# V3_B0317.net
KiCad netlist of a schematic drawn in Altium Designer
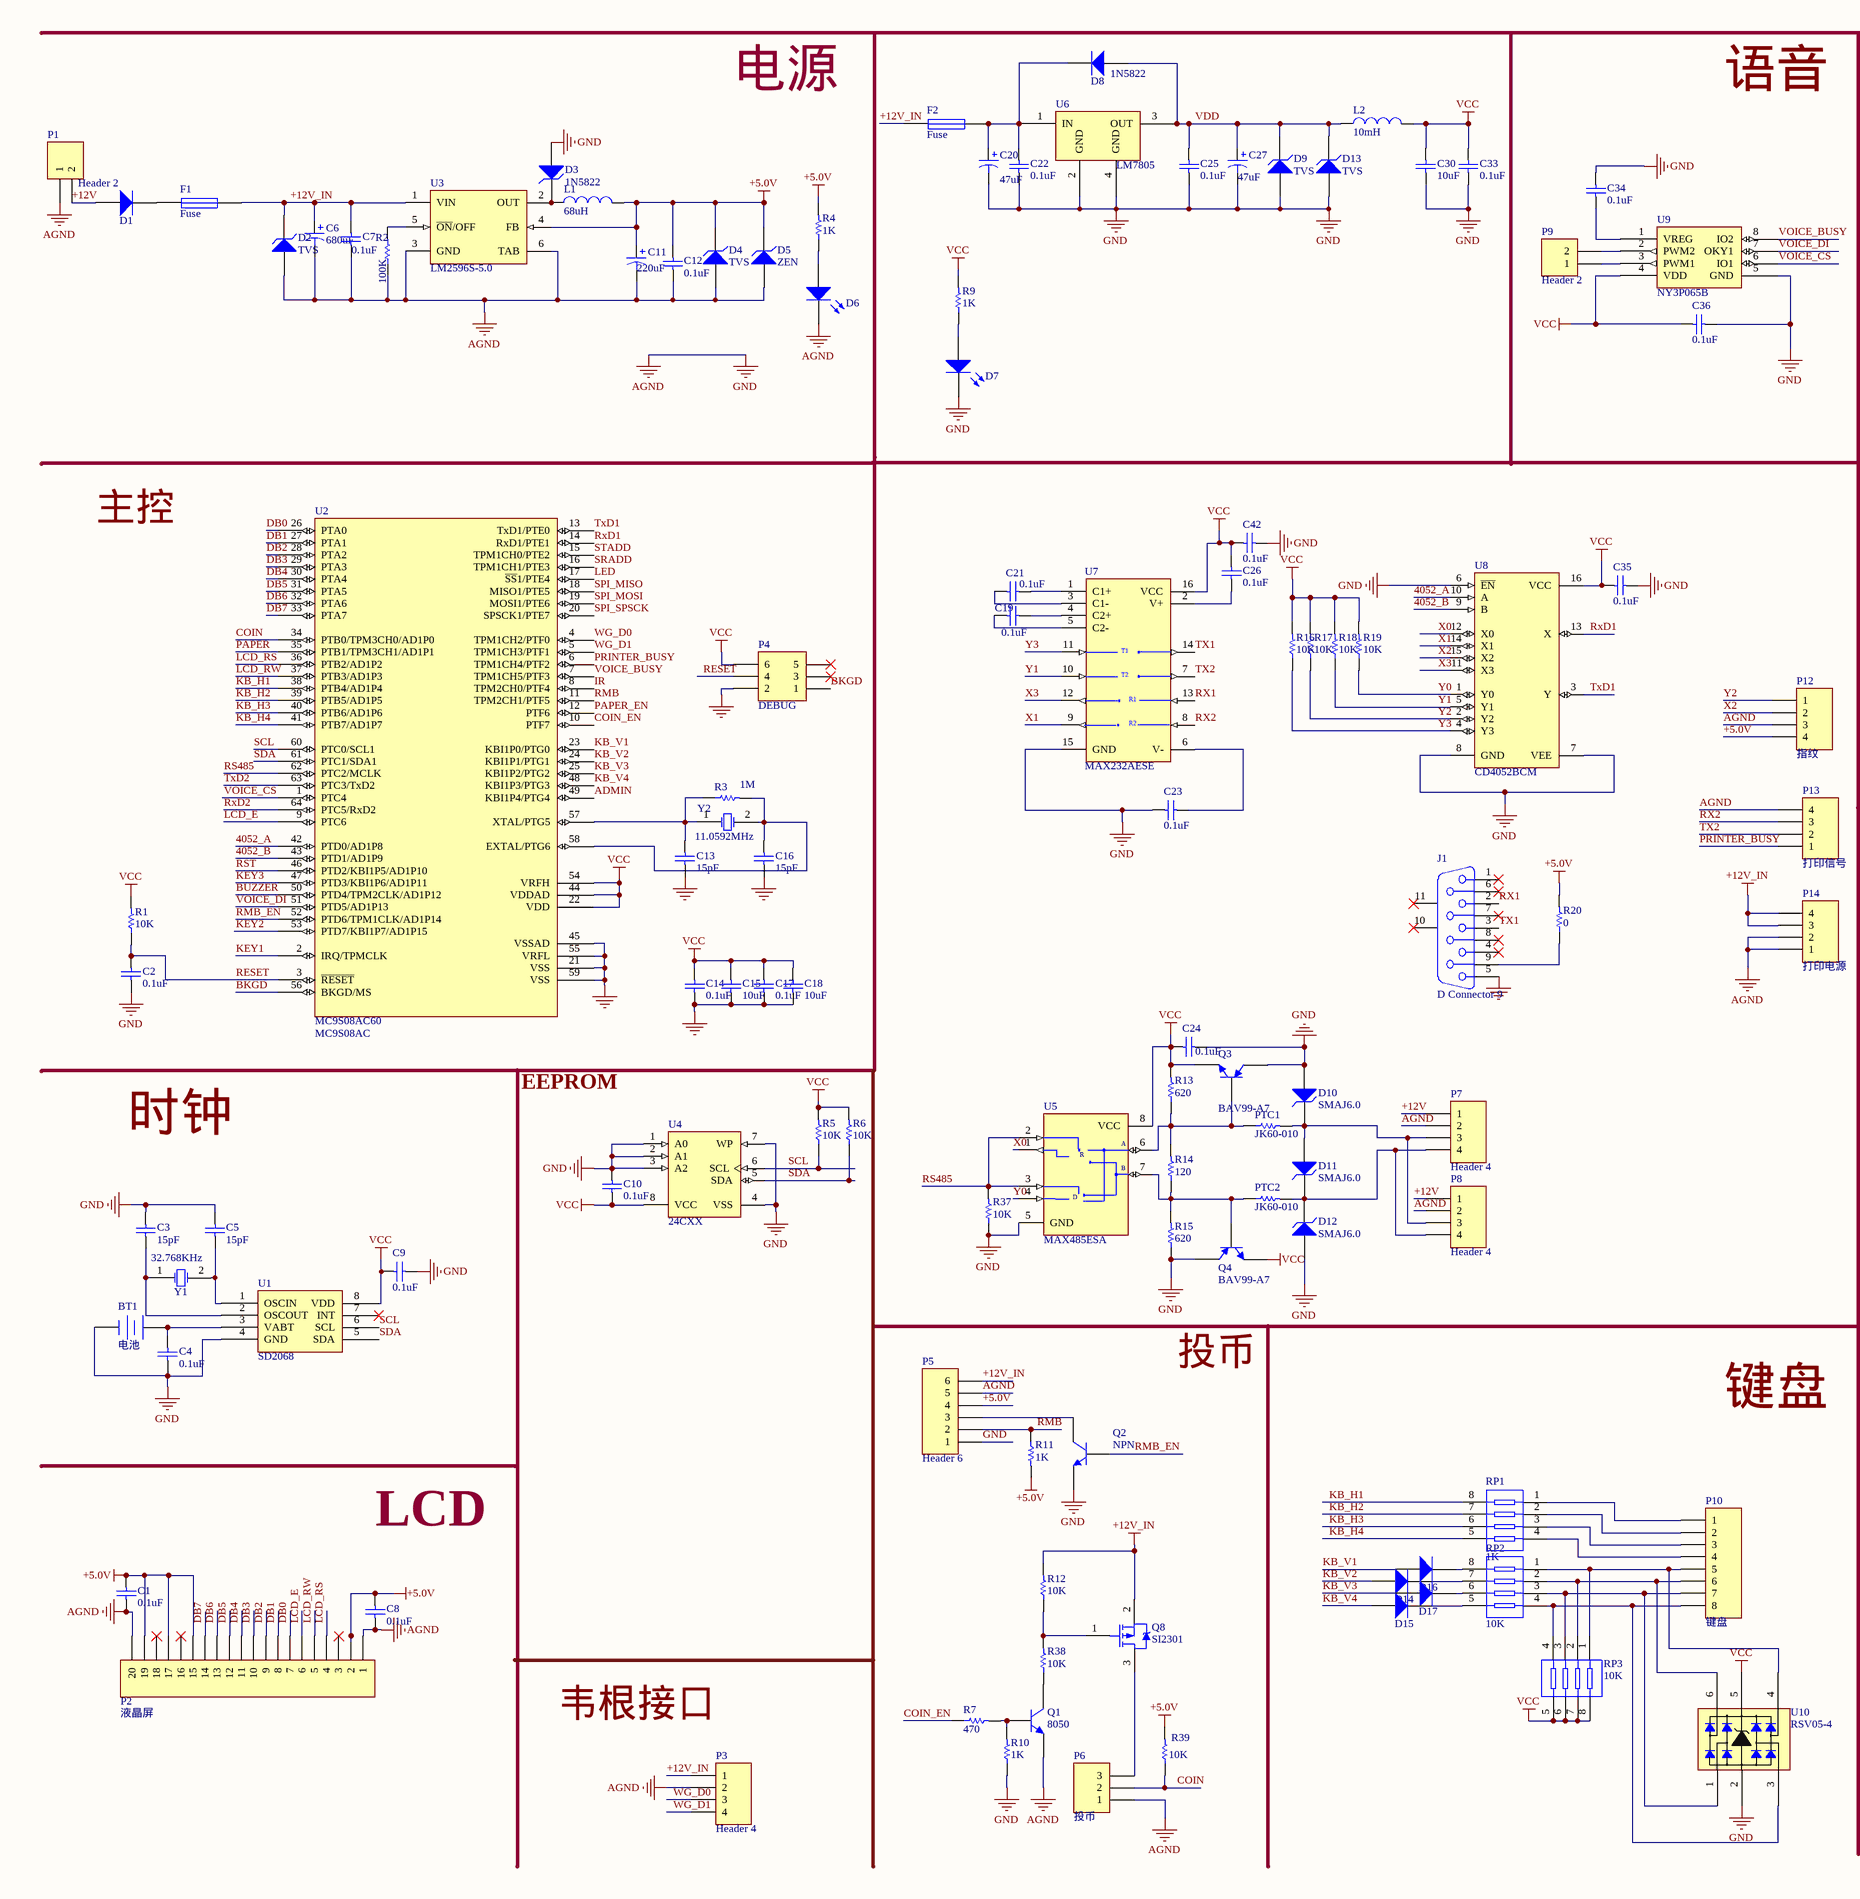
[diagram p0: V3(B0317).SchDoc, left]
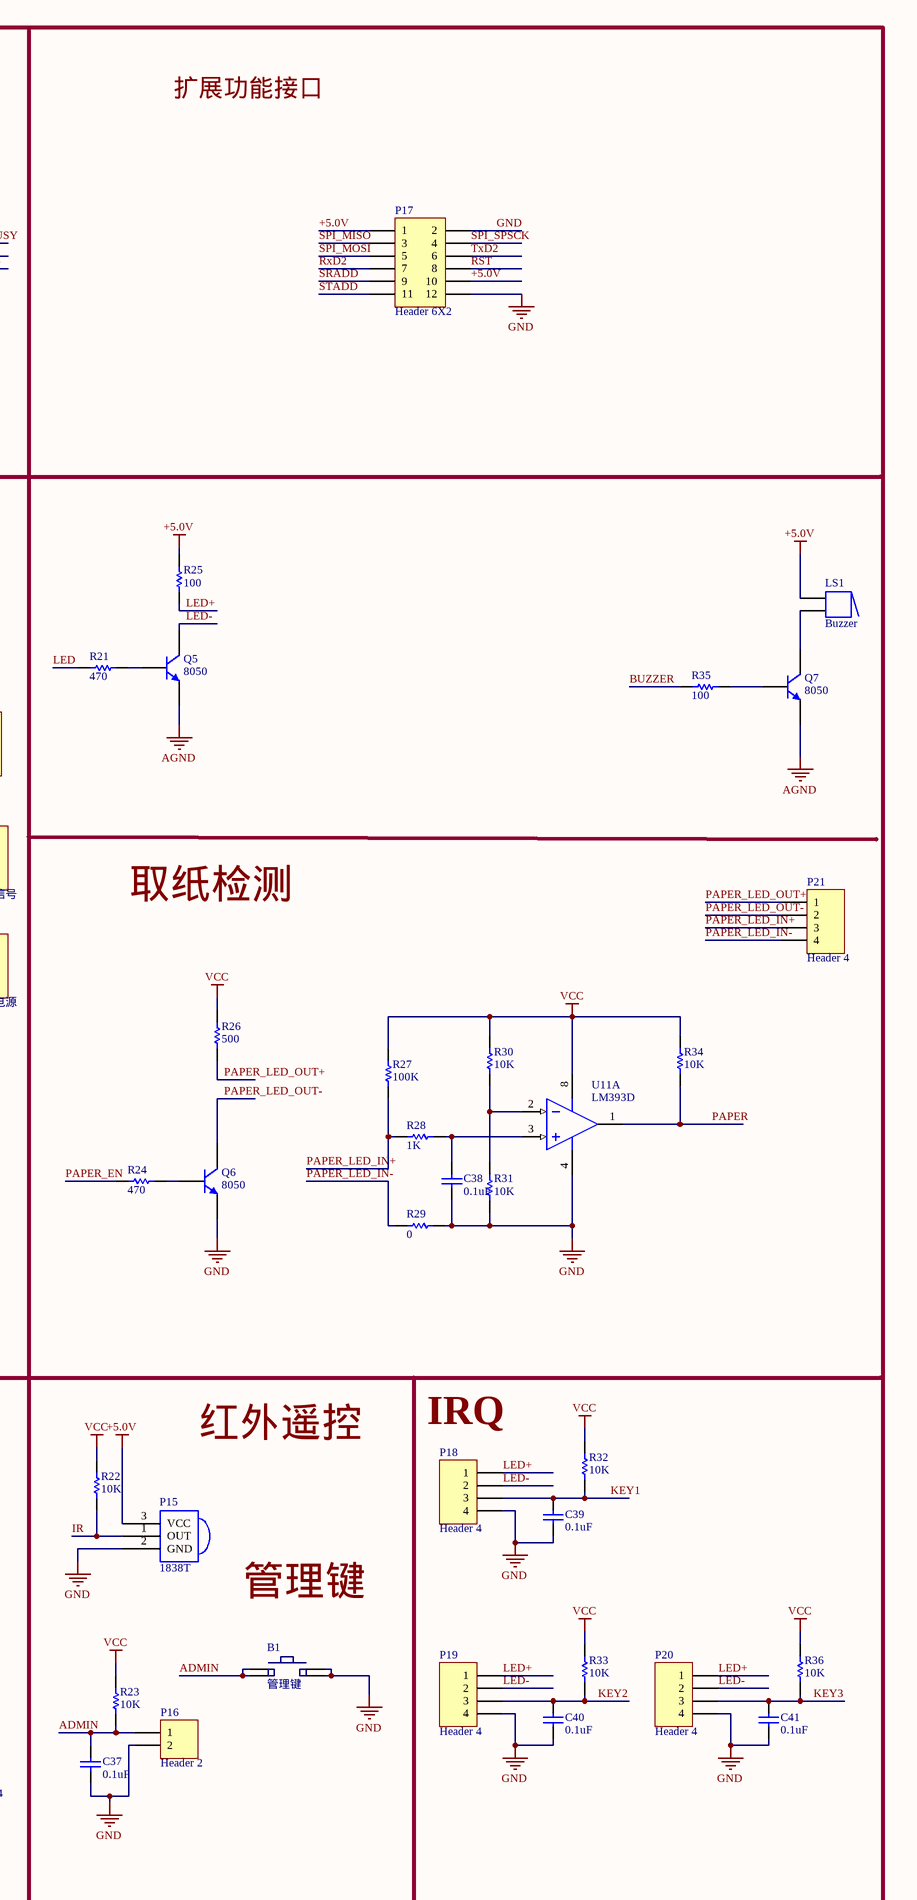
[diagram p1: V3(B0317).SchDoc, right]

(export (version "E")
  (design (tool "Eeschema 10.0.6"))
  (components
    (comp (ref "B1")
      (value "管理键")
      (footprint "AN66")
      (description "Button")
      (libsource (lib "device") (part "Button"))
    )
    (comp (ref "BT1")
      (value "电池")
      (footprint "CR1220")
      (description "Multicell Battery")
      (fields (field (name "PUBLISHER") "Altium Limited"))
      (libsource (lib "device") (part "Battery"))
    )
    (comp (ref "C1")
      (value "0.1uF")
      (footprint "CAPC2012M")
      (description "Capacitor")
      (fields (field (name "PUBLISHER") "Altium Limited"))
      (libsource (lib "device") (part "Cap"))
    )
    (comp (ref "C2")
      (value "0.1uF")
      (footprint "CAPC2012M")
      (description "Capacitor")
      (fields (field (name "PUBLISHER") "Altium Limited"))
      (libsource (lib "device") (part "Cap"))
    )
    (comp (ref "C3")
      (value "15pF")
      (footprint "CAPC2012M")
      (description "Capacitor")
      (fields (field (name "PUBLISHER") "Altium Limited"))
      (libsource (lib "device") (part "Cap"))
    )
    (comp (ref "C4")
      (value "0.1uF")
      (footprint "CAPC2012M")
      (description "Capacitor")
      (fields (field (name "PUBLISHER") "Altium Limited"))
      (libsource (lib "device") (part "Cap"))
    )
    (comp (ref "C5")
      (value "15pF")
      (footprint "CAPC2012M")
      (description "Capacitor")
      (fields (field (name "PUBLISHER") "Altium Limited"))
      (libsource (lib "device") (part "Cap"))
    )
    (comp (ref "C6")
      (value "680uF")
      (footprint "CAPPR2-5x11.5")
      (description "Polarized Capacitor (22uf-47uf)")
      (fields (field (name "Comment") "Cap Pol2") (field (name "PUBLISHER") "Altium Limited"))
      (libsource (lib "device") (part "Cap Pol2"))
    )
    (comp (ref "C7")
      (value "0.1uF")
      (footprint "CAPC2012M")
      (description "Capacitor")
      (fields (field (name "PUBLISHER") "Altium Limited"))
      (libsource (lib "device") (part "Cap"))
    )
    (comp (ref "C8")
      (value "0.1uF")
      (footprint "CAPC2012M")
      (description "Capacitor")
      (fields (field (name "PUBLISHER") "Altium Limited"))
      (libsource (lib "device") (part "Cap"))
    )
    (comp (ref "C9")
      (value "0.1uF")
      (footprint "CAPC2012M")
      (description "Capacitor")
      (fields (field (name "PUBLISHER") "Altium Limited"))
      (libsource (lib "device") (part "Cap"))
    )
    (comp (ref "C10")
      (value "0.1uF")
      (footprint "CAPC2012M")
      (description "Capacitor")
      (fields (field (name "PUBLISHER") "Altium Limited"))
      (libsource (lib "device") (part "Cap"))
    )
    (comp (ref "C11")
      (value "220uF")
      (footprint "CAPPR2-5x11.5")
      (description "Polarized Capacitor (22uf-47uf)")
      (fields (field (name "Comment") "Cap Pol2") (field (name "PUBLISHER") "Altium Limited"))
      (libsource (lib "device") (part "Cap Pol2"))
    )
    (comp (ref "C12")
      (value "0.1uF")
      (footprint "CAPC2012M")
      (description "Capacitor")
      (fields (field (name "PUBLISHER") "Altium Limited"))
      (libsource (lib "device") (part "Cap"))
    )
    (comp (ref "C13")
      (value "15pF")
      (footprint "CAPC2012M")
      (description "Capacitor")
      (fields (field (name "PUBLISHER") "Altium Limited"))
      (libsource (lib "device") (part "Cap"))
    )
    (comp (ref "C14")
      (value "0.1uF")
      (footprint "CAPC2012M")
      (description "Capacitor")
      (fields (field (name "PUBLISHER") "Altium Limited"))
      (libsource (lib "device") (part "Cap"))
    )
    (comp (ref "C15")
      (value "10uF")
      (footprint "CAPC2012M")
      (description "Capacitor")
      (fields (field (name "PUBLISHER") "Altium Limited"))
      (libsource (lib "device") (part "Cap"))
    )
    (comp (ref "C16")
      (value "15pF")
      (footprint "CAPC2012M")
      (description "Capacitor")
      (fields (field (name "PUBLISHER") "Altium Limited"))
      (libsource (lib "device") (part "Cap"))
    )
    (comp (ref "C17")
      (value "0.1uF")
      (footprint "CAPC2012M")
      (description "Capacitor")
      (fields (field (name "PUBLISHER") "Altium Limited"))
      (libsource (lib "device") (part "Cap"))
    )
    (comp (ref "C18")
      (value "10uF")
      (footprint "CAPC2012M")
      (description "Capacitor")
      (fields (field (name "PUBLISHER") "Altium Limited"))
      (libsource (lib "device") (part "Cap"))
    )
    (comp (ref "C19")
      (value "0.1uF")
      (footprint "CAPC2012M")
      (description "Capacitor")
      (fields (field (name "PUBLISHER") "Altium Limited"))
      (libsource (lib "device") (part "Cap"))
    )
    (comp (ref "C20")
      (value "47uF")
      (footprint "CAPPR2-5x11.5")
      (description "Polarized Capacitor (22uf-47uf)")
      (fields (field (name "Comment") "Cap Pol2") (field (name "PUBLISHER") "Altium Limited"))
      (libsource (lib "device") (part "Cap Pol2"))
    )
    (comp (ref "C21")
      (value "0.1uF")
      (footprint "CAPC2012M")
      (description "Capacitor")
      (fields (field (name "PUBLISHER") "Altium Limited"))
      (libsource (lib "device") (part "Cap"))
    )
    (comp (ref "C22")
      (value "0.1uF")
      (footprint "CAPC2012M")
      (description "Capacitor")
      (fields (field (name "PUBLISHER") "Altium Limited"))
      (libsource (lib "device") (part "Cap"))
    )
    (comp (ref "C23")
      (value "0.1uF")
      (footprint "CAPC2012M")
      (description "Capacitor")
      (fields (field (name "PUBLISHER") "Altium Limited"))
      (libsource (lib "device") (part "Cap"))
    )
    (comp (ref "C24")
      (value "0.1uF")
      (footprint "CAPC2012M")
      (description "Capacitor")
      (fields (field (name "PUBLISHER") "Altium Limited"))
      (libsource (lib "device") (part "Cap"))
    )
    (comp (ref "C25")
      (value "0.1uF")
      (footprint "CAPC2012M")
      (description "Capacitor")
      (fields (field (name "PUBLISHER") "Altium Limited"))
      (libsource (lib "device") (part "Cap"))
    )
    (comp (ref "C26")
      (value "0.1uF")
      (footprint "CAPC2012M")
      (description "Capacitor")
      (fields (field (name "PUBLISHER") "Altium Limited"))
      (libsource (lib "device") (part "Cap"))
    )
    (comp (ref "C27")
      (value "47uF")
      (footprint "CAPPR2-5x11.5")
      (description "Polarized Capacitor (22uf-47uf)")
      (fields (field (name "Comment") "Cap Pol2") (field (name "PUBLISHER") "Altium Limited"))
      (libsource (lib "device") (part "Cap Pol2"))
    )
    (comp (ref "C30")
      (value "10uF")
      (footprint "CAPC2012M")
      (description "Capacitor")
      (fields (field (name "PUBLISHER") "Altium Limited"))
      (libsource (lib "device") (part "Cap"))
    )
    (comp (ref "C33")
      (value "0.1uF")
      (footprint "CAPC2012M")
      (description "Capacitor")
      (fields (field (name "PUBLISHER") "Altium Limited"))
      (libsource (lib "device") (part "Cap"))
    )
    (comp (ref "C34")
      (value "0.1uF")
      (footprint "CAPC2012M")
      (description "Capacitor")
      (fields (field (name "PUBLISHER") "Altium Limited"))
      (libsource (lib "device") (part "Cap"))
    )
    (comp (ref "C35")
      (value "0.1uF")
      (footprint "CAPC2012M")
      (description "Capacitor")
      (fields (field (name "PUBLISHER") "Altium Limited"))
      (libsource (lib "device") (part "Cap"))
    )
    (comp (ref "C36")
      (value "0.1uF")
      (footprint "CAPC2012M")
      (description "Capacitor")
      (fields (field (name "PUBLISHER") "Altium Limited"))
      (libsource (lib "device") (part "Cap"))
    )
    (comp (ref "C37")
      (value "0.1uF")
      (footprint "CAPC2012M")
      (description "Capacitor")
      (fields (field (name "PUBLISHER") "Altium Limited"))
      (libsource (lib "device") (part "Cap"))
    )
    (comp (ref "C38")
      (value "0.1uF")
      (footprint "CAPC2012M")
      (description "Capacitor")
      (fields (field (name "PUBLISHER") "Altium Limited"))
      (libsource (lib "device") (part "Cap"))
    )
    (comp (ref "C39")
      (value "0.1uF")
      (footprint "CAPC2012M")
      (description "Capacitor")
      (fields (field (name "PUBLISHER") "Altium Limited"))
      (libsource (lib "device") (part "Cap"))
    )
    (comp (ref "C40")
      (value "0.1uF")
      (footprint "CAPC2012M")
      (description "Capacitor")
      (fields (field (name "PUBLISHER") "Altium Limited"))
      (libsource (lib "device") (part "Cap"))
    )
    (comp (ref "C41")
      (value "0.1uF")
      (footprint "CAPC2012M")
      (description "Capacitor")
      (fields (field (name "PUBLISHER") "Altium Limited"))
      (libsource (lib "device") (part "Cap"))
    )
    (comp (ref "C42")
      (value "0.1uF")
      (footprint "CAPC2012M")
      (description "Capacitor")
      (fields (field (name "PUBLISHER") "Altium Limited"))
      (libsource (lib "device") (part "Cap"))
    )
    (comp (ref "D1")
      (value "Diode")
      (footprint "DSO-C2/X1.8")
      (description "Default Diode")
      (fields (field (name "PUBLISHER") "Altium Limited"))
      (libsource (lib "device") (part "Diode"))
    )
    (comp (ref "D2")
      (value "TVS")
      (footprint "DSO-C2/X1.8")
      (description "TVS瞬态抑制二极管")
      (fields (field (name "PUBLISHER") "Altium Limited"))
      (libsource (lib "device") (part "TVS"))
    )
    (comp (ref "D3")
      (value "1N5822")
      (footprint "DSO-C2/X1.8")
      (description "TVS瞬态抑制二极管")
      (fields (field (name "PUBLISHER") "Altium Limited"))
      (libsource (lib "device") (part "TVS"))
    )
    (comp (ref "D4")
      (value "TVS")
      (footprint "DSO-C2/X1.8")
      (description "TVS瞬态抑制二极管")
      (fields (field (name "PUBLISHER") "Altium Limited"))
      (libsource (lib "device") (part "TVS"))
    )
    (comp (ref "D5")
      (value "ZEN")
      (footprint "DIO1206")
      (description "TVS瞬态抑制二极管")
      (fields (field (name "PUBLISHER") "Altium Limited"))
      (libsource (lib "device") (part "TVS"))
    )
    (comp (ref "D6")
      (value "LED")
      (footprint "LED2012M")
      (description "Typical INFRARED GaAs LED")
      (fields (field (name "PUBLISHER") "Altium Limited"))
      (libsource (lib "device") (part "LED"))
    )
    (comp (ref "D7")
      (value "LED")
      (footprint "LED2012M")
      (description "Typical INFRARED GaAs LED")
      (fields (field (name "PUBLISHER") "Altium Limited"))
      (libsource (lib "device") (part "LED"))
    )
    (comp (ref "D8")
      (value "1N5822")
      (footprint "DSO-C2/X1.8")
      (description "Default Diode")
      (fields (field (name "PUBLISHER") "Altium Limited"))
      (libsource (lib "device") (part "Diode"))
    )
    (comp (ref "D9")
      (value "TVS")
      (footprint "DSO-C2/X1.8")
      (description "TVS瞬态抑制二极管")
      (fields (field (name "PUBLISHER") "Altium Limited"))
      (libsource (lib "device") (part "TVS"))
    )
    (comp (ref "D10")
      (value "SMAJ6.0")
      (footprint "DSO-C2/X1.8")
      (description "TVS瞬态抑制二极管")
      (fields (field (name "PUBLISHER") "Altium Limited"))
      (libsource (lib "device") (part "TVS"))
    )
    (comp (ref "D11")
      (value "SMAJ6.0")
      (footprint "DSO-C2/X1.8")
      (description "TVS瞬态抑制二极管")
      (fields (field (name "PUBLISHER") "Altium Limited"))
      (libsource (lib "device") (part "TVS"))
    )
    (comp (ref "D12")
      (value "SMAJ6.0")
      (footprint "DSO-C2/X1.8")
      (description "TVS瞬态抑制二极管")
      (fields (field (name "PUBLISHER") "Altium Limited"))
      (libsource (lib "device") (part "TVS"))
    )
    (comp (ref "D13")
      (value "TVS")
      (footprint "DIO1206")
      (description "TVS瞬态抑制二极管")
      (fields (field (name "PUBLISHER") "Altium Limited"))
      (libsource (lib "device") (part "TVS"))
    )
    (comp (ref "D14")
      (value "1N4007")
      (footprint "SOD123")
      (description "Default Diode")
      (fields (field (name "PUBLISHER") "Altium Limited"))
      (libsource (lib "device") (part "Diode"))
    )
    (comp (ref "D15")
      (value "1N4007")
      (footprint "SOD123")
      (description "Default Diode")
      (fields (field (name "PUBLISHER") "Altium Limited"))
      (libsource (lib "device") (part "Diode"))
    )
    (comp (ref "D16")
      (value "1N4007")
      (footprint "SOD123")
      (description "Default Diode")
      (fields (field (name "PUBLISHER") "Altium Limited"))
      (libsource (lib "device") (part "Diode"))
    )
    (comp (ref "D17")
      (value "1N4007")
      (footprint "SOD123")
      (description "Default Diode")
      (fields (field (name "PUBLISHER") "Altium Limited"))
      (libsource (lib "device") (part "Diode"))
    )
    (comp (ref "F1")
      (value "Fuse")
      (footprint "SR075")
      (fields (field (name "PUBLISHER") "Altium Limited"))
      (libsource (lib "device") (part "Fuse"))
    )
    (comp (ref "F2")
      (value "Fuse")
      (footprint "FUSE1206N")
      (fields (field (name "PUBLISHER") "Altium Limited"))
      (libsource (lib "device") (part "Fuse"))
    )
    (comp (ref "J1")
      (value "D Connector 9")
      (footprint "DSUB1.385-2H9")
      (description "Receptacle Assembly, 9 Position, Right Angle")
      (fields (field (name "PUBLISHER") "Altium Limited"))
      (libsource (lib "connector") (part "D Connector 9"))
    )
    (comp (ref "L1")
      (value "68uH")
      (footprint "INDUCTOR-9*12")
      (description "Inductor")
      (fields (field (name "PUBLISHER") "Altium Limited"))
      (libsource (lib "device") (part "Inductor"))
    )
    (comp (ref "L2")
      (value "10mH")
      (footprint "INDC2012M")
      (description "Inductor")
      (fields (field (name "PUBLISHER") "Altium Limited"))
      (libsource (lib "device") (part "Inductor"))
    )
    (comp (ref "LS1")
      (value "Buzzer")
      (footprint "BELL")
      (description "Magnetic Transducer Buzzer")
      (fields (field (name "PUBLISHER") "Altium Limited"))
      (libsource (lib "device") (part "Buzzer"))
    )
    (comp (ref "P1")
      (value "Header 2")
      (footprint "VH396-2")
      (description "Header, 2-Pin")
      (fields (field (name "PUBLISHER") "Altium Limited"))
      (libsource (lib "") (part "Header 2_1"))
    )
    (comp (ref "P2")
      (value "液晶屏")
      (footprint "LCD12864")
      (description "Header, 20-Pin")
      (fields (field (name "PUBLISHER") "Altium Limited"))
      (libsource (lib "connector") (part "Header 20"))
    )
    (comp (ref "P3")
      (value "Header 4")
      (footprint "XH254-4")
      (description "Header, 4-Pin")
      (fields (field (name "PUBLISHER") "Altium Limited"))
      (libsource (lib "connector") (part "Header 4"))
    )
    (comp (ref "P4")
      (value "DEBUG")
      (footprint "HDR2X3")
      (description "Header, 3-Pin, Dual row")
      (fields (field (name "PUBLISHER") "Altium Limited"))
      (libsource (lib "connector") (part "Header 3X2"))
    )
    (comp (ref "P5")
      (value "Header 6")
      (footprint "XH254-6")
      (description "Header, 6-Pin")
      (fields (field (name "PUBLISHER") "Altium Limited"))
      (libsource (lib "connector") (part "Header 6"))
    )
    (comp (ref "P6")
      (value "投币")
      (footprint "XH254-3")
      (description "Header, 3-Pin")
      (fields (field (name "PUBLISHER") "Altium Limited"))
      (libsource (lib "connector") (part "Header 3"))
    )
    (comp (ref "P7")
      (value "Header 4")
      (footprint "VH396-4")
      (description "Header, 4-Pin")
      (fields (field (name "PUBLISHER") "Altium Limited"))
      (libsource (lib "connector") (part "Header 4"))
    )
    (comp (ref "P8")
      (value "Header 4")
      (footprint "VH396-4")
      (description "Header, 4-Pin")
      (fields (field (name "PUBLISHER") "Altium Limited"))
      (libsource (lib "connector") (part "Header 4"))
    )
    (comp (ref "P9")
      (value "Header 2")
      (footprint "XH254-2")
      (description "Header, 2-Pin")
      (fields (field (name "PUBLISHER") "Altium Limited"))
      (libsource (lib "connector") (part "Header 2"))
    )
    (comp (ref "P10")
      (value "键盘")
      (footprint "XH254-8")
      (description "Header, 8-Pin")
      (fields (field (name "PUBLISHER") "Altium Limited"))
      (libsource (lib "connector") (part "Header 8"))
    )
    (comp (ref "P12")
      (value "指纹")
      (footprint "XH254-4")
      (description "Header, 4-Pin")
      (fields (field (name "PUBLISHER") "Altium Limited"))
      (libsource (lib "connector") (part "Header 4"))
    )
    (comp (ref "P13")
      (value "打印信号")
      (footprint "XH254-4")
      (description "Header, 4-Pin")
      (fields (field (name "PUBLISHER") "Altium Limited"))
      (libsource (lib "") (part "Header 4_2"))
    )
    (comp (ref "P14")
      (value "打印电源")
      (footprint "XH254-4")
      (description "Header, 4-Pin")
      (fields (field (name "PUBLISHER") "Altium Limited"))
      (libsource (lib "") (part "Header 4_2"))
    )
    (comp (ref "P15") (value "1838T") (footprint "XH254-3") (libsource (lib "device") (part "1838T")))
    (comp (ref "P16")
      (value "Header 2")
      (footprint "XH254-2")
      (description "Header, 2-Pin")
      (fields (field (name "PUBLISHER") "Altium Limited"))
      (libsource (lib "") (part "Header 2_2"))
    )
    (comp (ref "P17")
      (value "Header 6X2")
      (footprint "HDR2X6")
      (description "Header, 6-Pin, Dual row")
      (fields (field (name "PUBLISHER") "Altium Limited"))
      (libsource (lib "Miscellaneous Connectors") (part "Header 6X2"))
    )
    (comp (ref "P18")
      (value "Header 4")
      (footprint "XH254-4")
      (description "Header, 4-Pin")
      (fields (field (name "PUBLISHER") "Altium Limited"))
      (libsource (lib "") (part "Header 4_1"))
    )
    (comp (ref "P19")
      (value "Header 4")
      (footprint "XH254-4")
      (description "Header, 4-Pin")
      (fields (field (name "PUBLISHER") "Altium Limited"))
      (libsource (lib "") (part "Header 4_1"))
    )
    (comp (ref "P20")
      (value "Header 4")
      (footprint "XH254-4")
      (description "Header, 4-Pin")
      (fields (field (name "PUBLISHER") "Altium Limited"))
      (libsource (lib "") (part "Header 4_1"))
    )
    (comp (ref "P21")
      (value "Header 4")
      (footprint "XH254-4")
      (description "Header, 4-Pin")
      (fields (field (name "PUBLISHER") "Altium Limited"))
      (libsource (lib "connector") (part "Header 4"))
    )
    (comp (ref "PTC1")
      (value "JK60-010")
      (footprint "RESC2012M")
      (description "Resistor")
      (fields (field (name "PUBLISHER") "Altium Limited"))
      (libsource (lib "device") (part "Res"))
    )
    (comp (ref "PTC2")
      (value "JK60-010")
      (footprint "RESC2012M")
      (description "Resistor")
      (fields (field (name "PUBLISHER") "Altium Limited"))
      (libsource (lib "device") (part "Res"))
    )
    (comp (ref "Q1")
      (value "8050")
      (footprint "SOT23-3M")
      (description "NPN Bipolar Transistor")
      (fields (field (name "PUBLISHER") "Altium Limited"))
      (libsource (lib "device") (part "NPN"))
    )
    (comp (ref "Q2")
      (value "NPN")
      (footprint "SOT23-3M")
      (description "NPN Bipolar Transistor")
      (fields (field (name "PUBLISHER") "Altium Limited"))
      (libsource (lib "device") (part "NPN"))
    )
    (comp (ref "Q3") (value "BAV99-A7") (footprint "SOT23-3M") (libsource (lib "device") (part "BAV99-A7")))
    (comp (ref "Q4") (value "BAV99-A7") (footprint "SOT23-3M") (libsource (lib "device") (part "BAV99-A7")))
    (comp (ref "Q5")
      (value "8050")
      (footprint "SOT23-3M")
      (description "NPN Bipolar Transistor")
      (fields (field (name "PUBLISHER") "Altium Limited"))
      (libsource (lib "device") (part "NPN"))
    )
    (comp (ref "Q6")
      (value "8050")
      (footprint "SOT23-3M")
      (description "NPN Bipolar Transistor")
      (fields (field (name "PUBLISHER") "Altium Limited"))
      (libsource (lib "device") (part "NPN"))
    )
    (comp (ref "Q7")
      (value "8050")
      (footprint "SOT23-3M")
      (description "NPN Bipolar Transistor")
      (fields (field (name "PUBLISHER") "Altium Limited"))
      (libsource (lib "device") (part "NPN"))
    )
    (comp (ref "Q8") (value "SI2301") (footprint "SOT23-3M") (libsource (lib "device") (part "SI2301")))
    (comp (ref "R1")
      (value "10K")
      (footprint "RESC2012M")
      (description "Resistor")
      (fields (field (name "PUBLISHER") "Altium Limited"))
      (libsource (lib "device") (part "Res"))
    )
    (comp (ref "R2")
      (value "100K")
      (footprint "RESC2012M")
      (description "Resistor")
      (fields (field (name "PUBLISHER") "Altium Limited"))
      (libsource (lib "device") (part "Res"))
    )
    (comp (ref "R3")
      (value "1M")
      (footprint "RESC2012M")
      (description "Resistor")
      (fields (field (name "PUBLISHER") "Altium Limited"))
      (libsource (lib "device") (part "Res"))
    )
    (comp (ref "R4")
      (value "1K")
      (footprint "RESC2012M")
      (description "Resistor")
      (fields (field (name "PUBLISHER") "Altium Limited"))
      (libsource (lib "device") (part "Res"))
    )
    (comp (ref "R5")
      (value "10K")
      (footprint "RESC2012M")
      (description "Resistor")
      (fields (field (name "PUBLISHER") "Altium Limited"))
      (libsource (lib "device") (part "Res"))
    )
    (comp (ref "R6")
      (value "10K")
      (footprint "RESC2012M")
      (description "Resistor")
      (fields (field (name "PUBLISHER") "Altium Limited"))
      (libsource (lib "device") (part "Res"))
    )
    (comp (ref "R7")
      (value "470")
      (footprint "RESC2012M")
      (description "Resistor")
      (fields (field (name "PUBLISHER") "Altium Limited"))
      (libsource (lib "device") (part "Res"))
    )
    (comp (ref "R9")
      (value "1K")
      (footprint "RESC2012M")
      (description "Resistor")
      (fields (field (name "PUBLISHER") "Altium Limited"))
      (libsource (lib "device") (part "Res"))
    )
    (comp (ref "R10")
      (value "1K")
      (footprint "RESC2012M")
      (description "Resistor")
      (fields (field (name "PUBLISHER") "Altium Limited"))
      (libsource (lib "device") (part "Res"))
    )
    (comp (ref "R11")
      (value "1K")
      (footprint "RESC2012M")
      (description "Resistor")
      (fields (field (name "PUBLISHER") "Altium Limited"))
      (libsource (lib "device") (part "Res"))
    )
    (comp (ref "R12")
      (value "10K")
      (footprint "RESC2012M")
      (description "Resistor")
      (fields (field (name "PUBLISHER") "Altium Limited"))
      (libsource (lib "device") (part "Res"))
    )
    (comp (ref "R13")
      (value "620")
      (footprint "RESC2012M")
      (description "Resistor")
      (fields (field (name "PUBLISHER") "Altium Limited"))
      (libsource (lib "device") (part "Res"))
    )
    (comp (ref "R14")
      (value "120")
      (footprint "RESC2012M")
      (description "Resistor")
      (fields (field (name "PUBLISHER") "Altium Limited"))
      (libsource (lib "device") (part "Res"))
    )
    (comp (ref "R15")
      (value "620")
      (footprint "RESC2012M")
      (description "Resistor")
      (fields (field (name "PUBLISHER") "Altium Limited"))
      (libsource (lib "device") (part "Res"))
    )
    (comp (ref "R16")
      (value "10K")
      (footprint "RESC2012M")
      (description "Resistor")
      (fields (field (name "PUBLISHER") "Altium Limited"))
      (libsource (lib "device") (part "Res"))
    )
    (comp (ref "R17")
      (value "10K")
      (footprint "RESC2012M")
      (description "Resistor")
      (fields (field (name "PUBLISHER") "Altium Limited"))
      (libsource (lib "device") (part "Res"))
    )
    (comp (ref "R18")
      (value "10K")
      (footprint "RESC2012M")
      (description "Resistor")
      (fields (field (name "PUBLISHER") "Altium Limited"))
      (libsource (lib "device") (part "Res"))
    )
    (comp (ref "R19")
      (value "10K")
      (footprint "RESC2012M")
      (description "Resistor")
      (fields (field (name "PUBLISHER") "Altium Limited"))
      (libsource (lib "device") (part "Res"))
    )
    (comp (ref "R20")
      (value "0")
      (footprint "RESC2012M")
      (description "Resistor")
      (fields (field (name "PUBLISHER") "Altium Limited"))
      (libsource (lib "device") (part "Res"))
    )
    (comp (ref "R21")
      (value "470")
      (footprint "RESC2012M")
      (description "Resistor")
      (fields (field (name "PUBLISHER") "Altium Limited"))
      (libsource (lib "device") (part "Res"))
    )
    (comp (ref "R22")
      (value "10K")
      (footprint "RESC2012M")
      (description "Resistor")
      (fields (field (name "PUBLISHER") "Altium Limited"))
      (libsource (lib "device") (part "Res"))
    )
    (comp (ref "R23")
      (value "10K")
      (footprint "RESC2012M")
      (description "Resistor")
      (fields (field (name "PUBLISHER") "Altium Limited"))
      (libsource (lib "device") (part "Res"))
    )
    (comp (ref "R24")
      (value "470")
      (footprint "RESC2012M")
      (description "Resistor")
      (fields (field (name "PUBLISHER") "Altium Limited"))
      (libsource (lib "device") (part "Res"))
    )
    (comp (ref "R25")
      (value "100")
      (footprint "RESC2012M")
      (description "Resistor")
      (fields (field (name "PUBLISHER") "Altium Limited"))
      (libsource (lib "device") (part "Res"))
    )
    (comp (ref "R26")
      (value "500")
      (footprint "RESC2012M")
      (description "Resistor")
      (fields (field (name "PUBLISHER") "Altium Limited"))
      (libsource (lib "device") (part "Res"))
    )
    (comp (ref "R27")
      (value "100K")
      (footprint "RESC2012M")
      (description "Resistor")
      (fields (field (name "PUBLISHER") "Altium Limited"))
      (libsource (lib "device") (part "Res"))
    )
    (comp (ref "R28")
      (value "1K")
      (footprint "RESC2012M")
      (description "Resistor")
      (fields (field (name "PUBLISHER") "Altium Limited"))
      (libsource (lib "device") (part "Res"))
    )
    (comp (ref "R29")
      (value "0")
      (footprint "RESC2012M")
      (description "Resistor")
      (fields (field (name "PUBLISHER") "Altium Limited"))
      (libsource (lib "device") (part "Res"))
    )
    (comp (ref "R30")
      (value "10K")
      (footprint "RESC2012M")
      (description "Resistor")
      (fields (field (name "PUBLISHER") "Altium Limited"))
      (libsource (lib "device") (part "Res"))
    )
    (comp (ref "R31")
      (value "10K")
      (footprint "RESC2012M")
      (description "Resistor")
      (fields (field (name "PUBLISHER") "Altium Limited"))
      (libsource (lib "device") (part "Res"))
    )
    (comp (ref "R32")
      (value "10K")
      (footprint "RESC2012M")
      (description "Resistor")
      (fields (field (name "PUBLISHER") "Altium Limited"))
      (libsource (lib "device") (part "Res"))
    )
    (comp (ref "R33")
      (value "10K")
      (footprint "RESC2012M")
      (description "Resistor")
      (fields (field (name "PUBLISHER") "Altium Limited"))
      (libsource (lib "device") (part "Res"))
    )
    (comp (ref "R34")
      (value "10K")
      (footprint "RESC2012M")
      (description "Resistor")
      (fields (field (name "PUBLISHER") "Altium Limited"))
      (libsource (lib "device") (part "Res"))
    )
    (comp (ref "R35")
      (value "100")
      (footprint "RESC2012M")
      (description "Resistor")
      (fields (field (name "PUBLISHER") "Altium Limited"))
      (libsource (lib "device") (part "Res"))
    )
    (comp (ref "R36")
      (value "10K")
      (footprint "RESC2012M")
      (description "Resistor")
      (fields (field (name "PUBLISHER") "Altium Limited"))
      (libsource (lib "device") (part "Res"))
    )
    (comp (ref "R37")
      (value "10K")
      (footprint "RESC2012M")
      (description "Resistor")
      (fields (field (name "PUBLISHER") "Altium Limited"))
      (libsource (lib "device") (part "Res"))
    )
    (comp (ref "R38")
      (value "10K")
      (footprint "RESC2012M")
      (description "Resistor")
      (fields (field (name "PUBLISHER") "Altium Limited"))
      (libsource (lib "device") (part "Res"))
    )
    (comp (ref "R39")
      (value "10K")
      (footprint "RESC2012M")
      (description "Resistor")
      (fields (field (name "PUBLISHER") "Altium Limited"))
      (libsource (lib "device") (part "Res"))
    )
    (comp (ref "RP1") (value "1K") (footprint "EXB38V") (libsource (lib "device") (part "Res Pack")))
    (comp (ref "RP2") (value "10K") (footprint "EXB38V") (libsource (lib "device") (part "Res Pack")))
    (comp (ref "RP3") (value "10K") (footprint "EXB38V") (libsource (lib "device") (part "Res Pack")))
    (comp (ref "U1")
      (value "SD2068")
      (footprint "SO8_M")
      (description "实时时钟")
      (libsource (lib "ic") (part "SD2068"))
    )
    (comp (ref "U2")
      (value "MC9S08AC60")
      (footprint "QFP80P1720X1720-64N")
      (description "HCS08 MC9S08AC60")
      (fields (field (name "ALTIUM_VALUE") "MC9S08AC"))
      (libsource (lib "ic") (part "MC9S08AC60"))
    )
    (comp (ref "U3")
      (value "LM2596S-5.0")
      (footprint "TS5B_N")
      (description "SIMPLE SWITCHER?Power Converter 150 KHz 3A Step-Down Voltage Regulator, 5-pin TO-263")
      (fields
        (field (name "MANUFACTURER") "National Semiconductor")
        (field (name "PUBLISHER") "Altium Limited")
      )
      (libsource (lib "ic") (part "LM2596S-5.0"))
    )
    (comp (ref "U4")
      (value "24CXX")
      (footprint "SO8_M")
      (description "5V, I2C Serial EEPROM")
      (fields (field (name "PUBLISHER") "Altium Limited"))
      (libsource (lib "ic") (part "24CXX"))
    )
    (comp (ref "U5")
      (value "MAX485ESA")
      (footprint "SO8_M")
      (description "Low-Power, Slew-Rate-Limited RS-485/RS-422 Transceiver")
      (fields (field (name "PUBLISHER") "Altium Limited"))
      (libsource (lib "ic") (part "MAX485ESA"))
    )
    (comp (ref "U6") (value "LM7805") (footprint "SOT223-4M") (libsource (lib "ic") (part "LM7805")))
    (comp (ref "U7")
      (value "MAX232AESE")
      (footprint "SO16_M")
      (description "+5V-Powered, Multichannel RS-232 Driver/Receiver")
      (fields (field (name "PUBLISHER") "Altium Limited"))
      (libsource (lib "ic") (part "MAX232AESE"))
    )
    (comp (ref "U8")
      (value "CD4052BCM")
      (footprint "SO16_M")
      (description "Dual 4-Channel Analog Multiplexer/Demultiplexer")
      (fields (field (name "PUBLISHER") "Altium Limited"))
      (libsource (lib "ic") (part "CD4052BCM"))
    )
    (comp (ref "U9") (value "NY3P065B") (footprint "DIP-8") (libsource (lib "ic") (part "NY3P065B")))
    (comp (ref "U10")
      (value "RSV05-4")
      (footprint "SOT26A-6M")
      (description "USB OR  Ethernet ESD")
      (libsource (lib "device") (part "RSV05-4"))
    )
    (comp (ref "U11")
      (value "LM393D")
      (footprint "SO8_M")
      (description "Low-Power Dual Voltage Comparator")
      (fields (field (name "PUBLISHER") "Altium Limited"))
      (libsource (lib "ic") (part "LM393D"))
    )
    (comp (ref "Y1")
      (value "32.768KHz")
      (footprint "XTAL-W2/D2.1")
      (description "Crystal Oscillator")
      (fields (field (name "Comment") "XTAL") (field (name "PUBLISHER") "Altium Limited"))
      (libsource (lib "device") (part "XTAL"))
    )
    (comp (ref "Y2")
      (value "11.0592MHz")
      (footprint "HC49_TH")
      (description "Crystal Oscillator")
      (fields (field (name "Comment") "XTAL") (field (name "PUBLISHER") "Altium Limited"))
      (libsource (lib "device") (part "XTAL"))
    )
  )
  (nets
    (net (code "1") (name "+5.0V") (class "Default")
      (node (ref "C1") (pin "2") (pinfunction "2_2") (pintype "passive"))
      (node (ref "C11") (pin "1") (pinfunction "1_1") (pintype "passive"))
      (node (ref "C12") (pin "2") (pinfunction "2_2") (pintype "passive"))
      (node (ref "C8") (pin "2") (pinfunction "2_2") (pintype "passive"))
      (node (ref "D4") (pin "2") (pinfunction "K_2") (pintype "passive"))
      (node (ref "D5") (pin "2") (pinfunction "K_2") (pintype "passive"))
      (node (ref "L1") (pin "2") (pinfunction "2_2") (pintype "passive"))
      (node (ref "LS1") (pin "1") (pinfunction "1_1") (pintype "passive"))
      (node (ref "P12") (pin "4") (pinfunction "4_4") (pintype "passive"))
      (node (ref "P15") (pin "3") (pinfunction "VCC_3") (pintype "passive"))
      (node (ref "P17") (pin "1") (pinfunction "1_1") (pintype "passive"))
      (node (ref "P17") (pin "10") (pinfunction "10_10") (pintype "passive"))
      (node (ref "P2") (pin "15") (pinfunction "15_15") (pintype "passive"))
      (node (ref "P2") (pin "17") (pinfunction "17_17") (pintype "passive"))
      (node (ref "P2") (pin "19") (pinfunction "19_19") (pintype "passive"))
      (node (ref "P2") (pin "2") (pinfunction "2_2") (pintype "passive"))
      (node (ref "P5") (pin "4") (pinfunction "4_4") (pintype "passive"))
      (node (ref "R11") (pin "2") (pinfunction "2_2") (pintype "passive"))
      (node (ref "R20") (pin "2") (pinfunction "2_2") (pintype "passive"))
      (node (ref "R25") (pin "2") (pinfunction "2_2") (pintype "passive"))
      (node (ref "R39") (pin "2") (pinfunction "2_2") (pintype "passive"))
      (node (ref "R4") (pin "2") (pinfunction "2_2") (pintype "passive"))
      (node (ref "U3") (pin "4") (pinfunction "FB_4") (pintype "input"))
    )
    (net (code "2") (name "+12V_IN") (class "Default")
      (node (ref "C6") (pin "1") (pinfunction "1_1") (pintype "passive"))
      (node (ref "C7") (pin "2") (pinfunction "2_2") (pintype "passive"))
      (node (ref "D2") (pin "2") (pinfunction "K_2") (pintype "passive"))
      (node (ref "F1") (pin "2") (pinfunction "2_2") (pintype "passive"))
      (node (ref "F2") (pin "1") (pinfunction "1_1") (pintype "passive"))
      (node (ref "P14") (pin "3") (pinfunction "3_3") (pintype "passive"))
      (node (ref "P14") (pin "4") (pinfunction "4_4") (pintype "passive"))
      (node (ref "P3") (pin "1") (pinfunction "1_1") (pintype "passive"))
      (node (ref "P5") (pin "6") (pinfunction "6_6") (pintype "passive"))
      (node (ref "Q8") (pin "2") (pinfunction "S_2") (pintype "passive"))
      (node (ref "R12") (pin "2") (pinfunction "2_2") (pintype "passive"))
      (node (ref "U3") (pin "1") (pinfunction "VIN_1") (pintype "power_in"))
    )
    (net (code "3") (name "/+12V") (class "Default")
      (node (ref "D1") (pin "1") (pinfunction "A_1") (pintype "passive"))
      (node (ref "P1") (pin "2") (pinfunction "2_2") (pintype "passive"))
      (node (ref "P7") (pin "1") (pinfunction "1_1") (pintype "passive"))
      (node (ref "P8") (pin "1") (pinfunction "1_1") (pintype "passive"))
    )
    (net (code "4") (name "/4052_A") (class "Default")
      (node (ref "U2") (pin "42") (pinfunction "PTD0/AD1P8_42") (pintype "bidirectional"))
      (node (ref "U8") (pin "10") (pinfunction "A_10") (pintype "input"))
    )
    (net (code "5") (name "/4052_B") (class "Default")
      (node (ref "U2") (pin "43") (pinfunction "PTD1/AD1P9_43") (pintype "bidirectional"))
      (node (ref "U8") (pin "9") (pinfunction "B_9") (pintype "input"))
    )
    (net (code "6") (name "/ADMIN") (class "Default")
      (node (ref "B1") (pin "1") (pintype "passive"))
      (node (ref "B1") (pin "3") (pintype "passive"))
      (node (ref "C37") (pin "2") (pinfunction "2_2") (pintype "passive"))
      (node (ref "P16") (pin "1") (pinfunction "1_1") (pintype "passive"))
      (node (ref "R23") (pin "1") (pinfunction "1_1") (pintype "passive"))
      (node (ref "U2") (pin "49") (pinfunction "KBI1P4/PTG4_49") (pintype "bidirectional"))
    )
    (net (code "7") (name "/BKGD") (class "Default")
      (node (ref "P4") (pin "1") (pinfunction "1_1") (pintype "passive"))
      (node (ref "U2") (pin "56") (pinfunction "BKGD/MS_56") (pintype "bidirectional"))
    )
    (net (code "8") (name "/BUZZER") (class "Default")
      (node (ref "R35") (pin "1") (pinfunction "1_1") (pintype "passive"))
      (node (ref "U2") (pin "50") (pinfunction "PTD4/TPM2CLK/AD1P12_50") (pintype "bidirectional"))
    )
    (net (code "9") (name "/COIN") (class "Default")
      (node (ref "P6") (pin "2") (pinfunction "2_2") (pintype "passive"))
      (node (ref "R39") (pin "1") (pinfunction "1_1") (pintype "passive"))
      (node (ref "U2") (pin "34") (pinfunction "PTB0/TPM3CH0/AD1P0_34") (pintype "bidirectional"))
    )
    (net (code "10") (name "/COIN_EN") (class "Default")
      (node (ref "R7") (pin "1") (pinfunction "1_1") (pintype "passive"))
      (node (ref "U2") (pin "10") (pinfunction "PTF7_10") (pintype "bidirectional"))
    )
    (net (code "11") (name "/DB0") (class "Default")
      (node (ref "P2") (pin "7") (pinfunction "7_7") (pintype "passive"))
      (node (ref "U2") (pin "26") (pinfunction "PTA0_26") (pintype "bidirectional"))
    )
    (net (code "12") (name "/DB1") (class "Default")
      (node (ref "P2") (pin "8") (pinfunction "8_8") (pintype "passive"))
      (node (ref "U2") (pin "27") (pinfunction "PTA1_27") (pintype "bidirectional"))
    )
    (net (code "13") (name "/DB2") (class "Default")
      (node (ref "P2") (pin "9") (pinfunction "9_9") (pintype "passive"))
      (node (ref "U2") (pin "28") (pinfunction "PTA2_28") (pintype "bidirectional"))
    )
    (net (code "14") (name "/DB3") (class "Default")
      (node (ref "P2") (pin "10") (pinfunction "10_10") (pintype "passive"))
      (node (ref "U2") (pin "29") (pinfunction "PTA3_29") (pintype "bidirectional"))
    )
    (net (code "15") (name "/DB4") (class "Default")
      (node (ref "P2") (pin "11") (pinfunction "11_11") (pintype "passive"))
      (node (ref "U2") (pin "30") (pinfunction "PTA4_30") (pintype "bidirectional"))
    )
    (net (code "16") (name "/DB5") (class "Default")
      (node (ref "P2") (pin "12") (pinfunction "12_12") (pintype "passive"))
      (node (ref "U2") (pin "31") (pinfunction "PTA5_31") (pintype "bidirectional"))
    )
    (net (code "17") (name "/DB6") (class "Default")
      (node (ref "P2") (pin "13") (pinfunction "13_13") (pintype "passive"))
      (node (ref "U2") (pin "32") (pinfunction "PTA6_32") (pintype "bidirectional"))
    )
    (net (code "18") (name "/DB7") (class "Default")
      (node (ref "P2") (pin "14") (pinfunction "14_14") (pintype "passive"))
      (node (ref "U2") (pin "33") (pinfunction "PTA7_33") (pintype "bidirectional"))
    )
    (net (code "19") (name "/IR") (class "Default")
      (node (ref "P15") (pin "1") (pinfunction "OUT_1") (pintype "passive"))
      (node (ref "R22") (pin "1") (pinfunction "1_1") (pintype "passive"))
      (node (ref "U2") (pin "8") (pinfunction "TPM2CH0/PTF4_8") (pintype "bidirectional"))
    )
    (net (code "20") (name "/KB_H1") (class "Default")
      (node (ref "RP1") (pin "8") (pinfunction "8_8") (pintype "passive"))
      (node (ref "U2") (pin "38") (pinfunction "PTB4/AD1P4_38") (pintype "bidirectional"))
    )
    (net (code "21") (name "/KB_H2") (class "Default")
      (node (ref "RP1") (pin "7") (pinfunction "7_7") (pintype "passive"))
      (node (ref "U2") (pin "39") (pinfunction "PTB5/AD1P5_39") (pintype "bidirectional"))
    )
    (net (code "22") (name "/KB_H3") (class "Default")
      (node (ref "RP1") (pin "6") (pinfunction "6_6") (pintype "passive"))
      (node (ref "U2") (pin "40") (pinfunction "PTB6/AD1P6_40") (pintype "bidirectional"))
    )
    (net (code "23") (name "/KB_H4") (class "Default")
      (node (ref "RP1") (pin "5") (pinfunction "5_5") (pintype "passive"))
      (node (ref "U2") (pin "41") (pinfunction "PTB7/AD1P7_41") (pintype "bidirectional"))
    )
    (net (code "24") (name "/KB_V1") (class "Default")
      (node (ref "D16") (pin "1") (pinfunction "A_1") (pintype "passive"))
      (node (ref "U2") (pin "23") (pinfunction "KBI1P0/PTG0_23") (pintype "bidirectional"))
    )
    (net (code "25") (name "/KB_V2") (class "Default")
      (node (ref "D14") (pin "1") (pinfunction "A_1") (pintype "passive"))
      (node (ref "U2") (pin "24") (pinfunction "KBI1P1/PTG1_24") (pintype "bidirectional"))
    )
    (net (code "26") (name "/KB_V3") (class "Default")
      (node (ref "D17") (pin "1") (pinfunction "A_1") (pintype "passive"))
      (node (ref "U2") (pin "25") (pinfunction "KBI1P2/PTG2_25") (pintype "bidirectional"))
    )
    (net (code "27") (name "/KB_V4") (class "Default")
      (node (ref "D15") (pin "1") (pinfunction "A_1") (pintype "passive"))
      (node (ref "U2") (pin "48") (pinfunction "KBI1P3/PTG3_48") (pintype "bidirectional"))
    )
    (net (code "28") (name "/KEY1") (class "Default")
      (node (ref "C39") (pin "2") (pinfunction "2_2") (pintype "passive"))
      (node (ref "P18") (pin "3") (pinfunction "3_3") (pintype "passive"))
      (node (ref "R32") (pin "1") (pinfunction "1_1") (pintype "passive"))
      (node (ref "U2") (pin "2") (pinfunction "IRQ/TPMCLK_2") (pintype "bidirectional"))
    )
    (net (code "29") (name "/KEY2") (class "Default")
      (node (ref "C40") (pin "2") (pinfunction "2_2") (pintype "passive"))
      (node (ref "P19") (pin "3") (pinfunction "3_3") (pintype "passive"))
      (node (ref "R33") (pin "1") (pinfunction "1_1") (pintype "passive"))
      (node (ref "U2") (pin "53") (pinfunction "PTD7/KBI1P7/AD1P15_53") (pintype "bidirectional"))
    )
    (net (code "30") (name "/KEY3") (class "Default")
      (node (ref "C41") (pin "2") (pinfunction "2_2") (pintype "passive"))
      (node (ref "P20") (pin "3") (pinfunction "3_3") (pintype "passive"))
      (node (ref "R36") (pin "1") (pinfunction "1_1") (pintype "passive"))
      (node (ref "U2") (pin "47") (pinfunction "PTD3/KBI1P6/AD1P11_47") (pintype "bidirectional"))
    )
    (net (code "31") (name "/LCD_E") (class "Default")
      (node (ref "P2") (pin "6") (pinfunction "6_6") (pintype "passive"))
      (node (ref "U2") (pin "9") (pinfunction "PTC6_9") (pintype "bidirectional"))
    )
    (net (code "32") (name "/LCD_RS") (class "Default")
      (node (ref "P2") (pin "4") (pinfunction "4_4") (pintype "passive"))
      (node (ref "U2") (pin "36") (pinfunction "PTB2/AD1P2_36") (pintype "bidirectional"))
    )
    (net (code "33") (name "/LCD_RW") (class "Default")
      (node (ref "P2") (pin "5") (pinfunction "5_5") (pintype "passive"))
      (node (ref "U2") (pin "37") (pinfunction "PTB3/AD1P3_37") (pintype "bidirectional"))
    )
    (net (code "34") (name "/LED") (class "Default")
      (node (ref "R21") (pin "1") (pinfunction "1_1") (pintype "passive"))
      (node (ref "U2") (pin "17") (pinfunction "~{SS}1/PTE4_17") (pintype "bidirectional"))
    )
    (net (code "35") (name "/LED+") (class "Default")
      (node (ref "P18") (pin "1") (pinfunction "1_1") (pintype "passive"))
      (node (ref "P19") (pin "1") (pinfunction "1_1") (pintype "passive"))
      (node (ref "P20") (pin "1") (pinfunction "1_1") (pintype "passive"))
      (node (ref "R25") (pin "1") (pinfunction "1_1") (pintype "passive"))
    )
    (net (code "36") (name "/LED-") (class "Default")
      (node (ref "P18") (pin "2") (pinfunction "2_2") (pintype "passive"))
      (node (ref "P19") (pin "2") (pinfunction "2_2") (pintype "passive"))
      (node (ref "P20") (pin "2") (pinfunction "2_2") (pintype "passive"))
      (node (ref "Q5") (pin "3") (pinfunction "C_3") (pintype "passive"))
    )
    (net (code "37") (name "/PAPER") (class "Default")
      (node (ref "R34") (pin "1") (pinfunction "1_1") (pintype "passive"))
      (node (ref "U11") (pin "1") (pinfunction "OUT_1") (pintype "open_collector"))
      (node (ref "U2") (pin "35") (pinfunction "PTB1/TPM3CH1/AD1P1_35") (pintype "bidirectional"))
    )
    (net (code "38") (name "/PAPER_EN") (class "Default")
      (node (ref "R24") (pin "1") (pinfunction "1_1") (pintype "passive"))
      (node (ref "U2") (pin "12") (pinfunction "PTF6_12") (pintype "bidirectional"))
    )
    (net (code "39") (name "/PAPER_LED_IN+") (class "Default")
      (node (ref "P21") (pin "3") (pinfunction "3_3") (pintype "passive"))
      (node (ref "R27") (pin "1") (pinfunction "1_1") (pintype "passive"))
      (node (ref "R28") (pin "1") (pinfunction "1_1") (pintype "passive"))
    )
    (net (code "40") (name "/PAPER_LED_IN-") (class "Default")
      (node (ref "P21") (pin "4") (pinfunction "4_4") (pintype "passive"))
      (node (ref "R29") (pin "1") (pinfunction "1_1") (pintype "passive"))
    )
    (net (code "41") (name "/PAPER_LED_OUT+") (class "Default")
      (node (ref "P21") (pin "1") (pinfunction "1_1") (pintype "passive"))
      (node (ref "R26") (pin "1") (pinfunction "1_1") (pintype "passive"))
    )
    (net (code "42") (name "/PAPER_LED_OUT-") (class "Default")
      (node (ref "P21") (pin "2") (pinfunction "2_2") (pintype "passive"))
      (node (ref "Q6") (pin "3") (pinfunction "C_3") (pintype "passive"))
    )
    (net (code "43") (name "/PRINTER_BUSY") (class "Default")
      (node (ref "P13") (pin "1") (pinfunction "1_1") (pintype "passive"))
      (node (ref "U2") (pin "6") (pinfunction "TPM1CH4/PTF2_6") (pintype "bidirectional"))
    )
    (net (code "44") (name "/RESET") (class "Default")
      (node (ref "C2") (pin "2") (pinfunction "2_2") (pintype "passive"))
      (node (ref "P4") (pin "4") (pinfunction "4_4") (pintype "passive"))
      (node (ref "R1") (pin "1") (pinfunction "1_1") (pintype "passive"))
      (node (ref "U2") (pin "3") (pinfunction "~{RESET}_3") (pintype "bidirectional"))
    )
    (net (code "45") (name "/RMB") (class "Default")
      (node (ref "P5") (pin "2") (pinfunction "2_2") (pintype "passive"))
      (node (ref "R11") (pin "1") (pinfunction "1_1") (pintype "passive"))
      (node (ref "U2") (pin "11") (pinfunction "TPM2CH1/PTF5_11") (pintype "bidirectional"))
    )
    (net (code "46") (name "/RMB_EN") (class "Default")
      (node (ref "Q2") (pin "1") (pinfunction "B_1") (pintype "passive"))
      (node (ref "U2") (pin "52") (pinfunction "PTD6/TPM1CLK/AD1P14_52") (pintype "bidirectional"))
    )
    (net (code "47") (name "/RS485") (class "Default")
      (node (ref "R37") (pin "2") (pinfunction "2_2") (pintype "passive"))
      (node (ref "U2") (pin "62") (pinfunction "PTC2/MCLK_62") (pintype "bidirectional"))
      (node (ref "U5") (pin "2") (pinfunction "~{RE}_2") (pintype "input"))
      (node (ref "U5") (pin "3") (pinfunction "DE_3") (pintype "input"))
    )
    (net (code "48") (name "/RST") (class "Default")
      (node (ref "P17") (pin "8") (pinfunction "8_8") (pintype "passive"))
      (node (ref "U2") (pin "46") (pinfunction "PTD2/KBI1P5/AD1P10_46") (pintype "bidirectional"))
    )
    (net (code "49") (name "/RX1") (class "Default")
      (node (ref "J1") (pin "2") (pinfunction "2_2") (pintype "passive"))
      (node (ref "U7") (pin "13") (pinfunction "R1IN_13") (pintype "input"))
    )
    (net (code "50") (name "/RX2") (class "Default")
      (node (ref "P13") (pin "3") (pinfunction "3_3") (pintype "passive"))
      (node (ref "U7") (pin "8") (pinfunction "R2IN_8") (pintype "input"))
    )
    (net (code "51") (name "/RxD1") (class "Default")
      (node (ref "U2") (pin "14") (pinfunction "RxD1/PTE1_14") (pintype "bidirectional"))
      (node (ref "U8") (pin "13") (pinfunction "X_13") (pintype "bidirectional"))
    )
    (net (code "52") (name "/RxD2") (class "Default")
      (node (ref "P17") (pin "7") (pinfunction "7_7") (pintype "passive"))
      (node (ref "U2") (pin "64") (pinfunction "PTC5/RxD2_64") (pintype "bidirectional"))
    )
    (net (code "53") (name "/SCL") (class "Default")
      (node (ref "R5") (pin "1") (pinfunction "1_1") (pintype "passive"))
      (node (ref "U1") (pin "6") (pinfunction "SCL_6") (pintype "passive"))
      (node (ref "U2") (pin "60") (pinfunction "PTC0/SCL1_60") (pintype "bidirectional"))
      (node (ref "U4") (pin "6") (pinfunction "SCL_6") (pintype "input"))
    )
    (net (code "54") (name "/SDA") (class "Default")
      (node (ref "R6") (pin "1") (pinfunction "1_1") (pintype "passive"))
      (node (ref "U1") (pin "5") (pinfunction "SDA_5") (pintype "passive"))
      (node (ref "U2") (pin "61") (pinfunction "PTC1/SDA1_61") (pintype "bidirectional"))
      (node (ref "U4") (pin "5") (pinfunction "SDA_5") (pintype "bidirectional"))
    )
    (net (code "55") (name "/SPI_MISO") (class "Default")
      (node (ref "P17") (pin "3") (pinfunction "3_3") (pintype "passive"))
      (node (ref "U2") (pin "18") (pinfunction "MISO1/PTE5_18") (pintype "bidirectional"))
    )
    (net (code "56") (name "/SPI_MOSI") (class "Default")
      (node (ref "P17") (pin "5") (pinfunction "5_5") (pintype "passive"))
      (node (ref "U2") (pin "19") (pinfunction "MOSI1/PTE6_19") (pintype "bidirectional"))
    )
    (net (code "57") (name "/SPI_SPSCK") (class "Default")
      (node (ref "P17") (pin "4") (pinfunction "4_4") (pintype "passive"))
      (node (ref "U2") (pin "20") (pinfunction "SPSCK1/PTE7_20") (pintype "bidirectional"))
    )
    (net (code "58") (name "/SRADD") (class "Default")
      (node (ref "P17") (pin "9") (pinfunction "9_9") (pintype "passive"))
      (node (ref "U2") (pin "16") (pinfunction "TPM1CH1/PTE3_16") (pintype "bidirectional"))
    )
    (net (code "59") (name "/STADD") (class "Default")
      (node (ref "P17") (pin "11") (pinfunction "11_11") (pintype "passive"))
      (node (ref "U2") (pin "15") (pinfunction "TPM1CH0/PTE2_15") (pintype "bidirectional"))
    )
    (net (code "60") (name "/TX1") (class "Default")
      (node (ref "J1") (pin "3") (pinfunction "3_3") (pintype "passive"))
      (node (ref "U7") (pin "14") (pinfunction "T1OUT_14") (pintype "output"))
    )
    (net (code "61") (name "/TX2") (class "Default")
      (node (ref "P13") (pin "2") (pinfunction "2_2") (pintype "passive"))
      (node (ref "U7") (pin "7") (pinfunction "T2OUT_7") (pintype "output"))
    )
    (net (code "62") (name "/TxD1") (class "Default")
      (node (ref "U2") (pin "13") (pinfunction "TxD1/PTE0_13") (pintype "bidirectional"))
      (node (ref "U8") (pin "3") (pinfunction "Y_3") (pintype "bidirectional"))
    )
    (net (code "63") (name "/TxD2") (class "Default")
      (node (ref "P17") (pin "6") (pinfunction "6_6") (pintype "passive"))
      (node (ref "U2") (pin "63") (pinfunction "PTC3/TxD2_63") (pintype "bidirectional"))
    )
    (net (code "64") (name "/VDD") (class "Default")
      (node (ref "C25") (pin "1") (pinfunction "1_1") (pintype "passive"))
      (node (ref "C27") (pin "1") (pinfunction "1_1") (pintype "passive"))
      (node (ref "D13") (pin "2") (pinfunction "K_2") (pintype "passive"))
      (node (ref "D8") (pin "1") (pinfunction "A_1") (pintype "passive"))
      (node (ref "D9") (pin "2") (pinfunction "K_2") (pintype "passive"))
      (node (ref "L2") (pin "1") (pinfunction "1_1") (pintype "passive"))
      (node (ref "U6") (pin "3") (pinfunction "OUT_3") (pintype "passive"))
    )
    (net (code "65") (name "/VOICE_BUSY") (class "Default")
      (node (ref "U2") (pin "7") (pinfunction "TPM1CH5/PTF3_7") (pintype "bidirectional"))
      (node (ref "U9") (pin "8") (pinfunction "IO2_8") (pintype "bidirectional"))
    )
    (net (code "66") (name "/VOICE_CS") (class "Default")
      (node (ref "U2") (pin "1") (pinfunction "PTC4_1") (pintype "bidirectional"))
      (node (ref "U9") (pin "6") (pinfunction "IO1_6") (pintype "bidirectional"))
    )
    (net (code "67") (name "/VOICE_DI") (class "Default")
      (node (ref "U2") (pin "51") (pinfunction "PTD5/AD1P13_51") (pintype "bidirectional"))
      (node (ref "U9") (pin "7") (pinfunction "OKY1_7") (pintype "bidirectional"))
    )
    (net (code "68") (name "/WG_D0") (class "Default")
      (node (ref "P3") (pin "3") (pinfunction "3_3") (pintype "passive"))
      (node (ref "U2") (pin "4") (pinfunction "TPM1CH2/PTF0_4") (pintype "bidirectional"))
    )
    (net (code "69") (name "/WG_D1") (class "Default")
      (node (ref "P3") (pin "4") (pinfunction "4_4") (pintype "passive"))
      (node (ref "U2") (pin "5") (pinfunction "TPM1CH3/PTF1_5") (pintype "bidirectional"))
    )
    (net (code "70") (name "/X0") (class "Default")
      (node (ref "U5") (pin "1") (pinfunction "RO_1") (pintype "output"))
      (node (ref "U8") (pin "12") (pinfunction "X0_12") (pintype "bidirectional"))
    )
    (net (code "71") (name "/X1") (class "Default")
      (node (ref "U7") (pin "9") (pinfunction "R2OUT_9") (pintype "output"))
      (node (ref "U8") (pin "14") (pinfunction "X1_14") (pintype "bidirectional"))
    )
    (net (code "72") (name "/X2") (class "Default")
      (node (ref "P12") (pin "2") (pinfunction "2_2") (pintype "passive"))
      (node (ref "U8") (pin "15") (pinfunction "X2_15") (pintype "bidirectional"))
    )
    (net (code "73") (name "/X3") (class "Default")
      (node (ref "U7") (pin "12") (pinfunction "R1OUT_12") (pintype "output"))
      (node (ref "U8") (pin "11") (pinfunction "X3_11") (pintype "bidirectional"))
    )
    (net (code "74") (name "/Y0") (class "Default")
      (node (ref "R19") (pin "1") (pinfunction "1_1") (pintype "passive"))
      (node (ref "U5") (pin "4") (pinfunction "DI_4") (pintype "input"))
      (node (ref "U8") (pin "1") (pinfunction "Y0_1") (pintype "bidirectional"))
    )
    (net (code "75") (name "/Y1") (class "Default")
      (node (ref "R18") (pin "1") (pinfunction "1_1") (pintype "passive"))
      (node (ref "U7") (pin "10") (pinfunction "T2IN_10") (pintype "input"))
      (node (ref "U8") (pin "5") (pinfunction "Y1_5") (pintype "bidirectional"))
    )
    (net (code "76") (name "/Y2") (class "Default")
      (node (ref "P12") (pin "1") (pinfunction "1_1") (pintype "passive"))
      (node (ref "R17") (pin "1") (pinfunction "1_1") (pintype "passive"))
      (node (ref "U8") (pin "2") (pinfunction "Y2_2") (pintype "bidirectional"))
    )
    (net (code "77") (name "/Y3") (class "Default")
      (node (ref "R16") (pin "1") (pinfunction "1_1") (pintype "passive"))
      (node (ref "U7") (pin "11") (pinfunction "T1IN_11") (pintype "input"))
      (node (ref "U8") (pin "4") (pinfunction "Y3_4") (pintype "bidirectional"))
    )
    (net (code "78") (name "AGND") (class "Default")
      (node (ref "B1") (pin "2") (pintype "passive"))
      (node (ref "B1") (pin "4") (pintype "passive"))
      (node (ref "BT1") (pin "2") (pinfunction "-_2") (pintype "passive"))
      (node (ref "C1") (pin "1") (pinfunction "1_1") (pintype "passive"))
      (node (ref "C10") (pin "2") (pinfunction "2_2") (pintype "passive"))
      (node (ref "C11") (pin "2") (pinfunction "2_2") (pintype "passive"))
      (node (ref "C12") (pin "1") (pinfunction "1_1") (pintype "passive"))
      (node (ref "C13") (pin "1") (pinfunction "1_1") (pintype "passive"))
      (node (ref "C14") (pin "1") (pinfunction "1_1") (pintype "passive"))
      (node (ref "C15") (pin "1") (pinfunction "1_1") (pintype "passive"))
      (node (ref "C16") (pin "1") (pinfunction "1_1") (pintype "passive"))
      (node (ref "C17") (pin "1") (pinfunction "1_1") (pintype "passive"))
      (node (ref "C18") (pin "1") (pinfunction "1_1") (pintype "passive"))
      (node (ref "C2") (pin "1") (pinfunction "1_1") (pintype "passive"))
      (node (ref "C20") (pin "2") (pinfunction "2_2") (pintype "passive"))
      (node (ref "C22") (pin "1") (pinfunction "1_1") (pintype "passive"))
      (node (ref "C23") (pin "1") (pinfunction "1_1") (pintype "passive"))
      (node (ref "C24") (pin "2") (pinfunction "2_2") (pintype "passive"))
      (node (ref "C25") (pin "2") (pinfunction "2_2") (pintype "passive"))
      (node (ref "C27") (pin "2") (pinfunction "2_2") (pintype "passive"))
      (node (ref "C3") (pin "2") (pinfunction "2_2") (pintype "passive"))
      (node (ref "C30") (pin "1") (pinfunction "1_1") (pintype "passive"))
      (node (ref "C33") (pin "1") (pinfunction "1_1") (pintype "passive"))
      (node (ref "C34") (pin "2") (pinfunction "2_2") (pintype "passive"))
      (node (ref "C35") (pin "2") (pinfunction "2_2") (pintype "passive"))
      (node (ref "C36") (pin "1") (pinfunction "1_1") (pintype "passive"))
      (node (ref "C37") (pin "1") (pinfunction "1_1") (pintype "passive"))
      (node (ref "C38") (pin "1") (pinfunction "1_1") (pintype "passive"))
      (node (ref "C39") (pin "1") (pinfunction "1_1") (pintype "passive"))
      (node (ref "C4") (pin "1") (pinfunction "1_1") (pintype "passive"))
      (node (ref "C40") (pin "1") (pinfunction "1_1") (pintype "passive"))
      (node (ref "C41") (pin "1") (pinfunction "1_1") (pintype "passive"))
      (node (ref "C42") (pin "2") (pinfunction "2_2") (pintype "passive"))
      (node (ref "C5") (pin "2") (pinfunction "2_2") (pintype "passive"))
      (node (ref "C6") (pin "2") (pinfunction "2_2") (pintype "passive"))
      (node (ref "C7") (pin "1") (pinfunction "1_1") (pintype "passive"))
      (node (ref "C8") (pin "1") (pinfunction "1_1") (pintype "passive"))
      (node (ref "C9") (pin "2") (pinfunction "2_2") (pintype "passive"))
      (node (ref "D10") (pin "1") (pinfunction "A_1") (pintype "passive"))
      (node (ref "D12") (pin "1") (pinfunction "A_1") (pintype "passive"))
      (node (ref "D13") (pin "1") (pinfunction "A_1") (pintype "passive"))
      (node (ref "D2") (pin "1") (pinfunction "A_1") (pintype "passive"))
      (node (ref "D3") (pin "1") (pinfunction "A_1") (pintype "passive"))
      (node (ref "D4") (pin "1") (pinfunction "A_1") (pintype "passive"))
      (node (ref "D5") (pin "1") (pinfunction "A_1") (pintype "passive"))
      (node (ref "D6") (pin "2") (pinfunction "K_2") (pintype "passive"))
      (node (ref "D7") (pin "2") (pinfunction "K_2") (pintype "passive"))
      (node (ref "D9") (pin "1") (pinfunction "A_1") (pintype "passive"))
      (node (ref "J1") (pin "5") (pinfunction "5_5") (pintype "passive"))
      (node (ref "P1") (pin "1") (pinfunction "1_1") (pintype "passive"))
      (node (ref "P12") (pin "3") (pinfunction "3_3") (pintype "passive"))
      (node (ref "P13") (pin "4") (pinfunction "4_4") (pintype "passive"))
      (node (ref "P14") (pin "1") (pinfunction "1_1") (pintype "passive"))
      (node (ref "P14") (pin "2") (pinfunction "2_2") (pintype "passive"))
      (node (ref "P15") (pin "2") (pinfunction "GND_2") (pintype "passive"))
      (node (ref "P16") (pin "2") (pinfunction "2_2") (pintype "passive"))
      (node (ref "P17") (pin "12") (pinfunction "12_12") (pintype "passive"))
      (node (ref "P17") (pin "2") (pinfunction "2_2") (pintype "passive"))
      (node (ref "P18") (pin "4") (pinfunction "4_4") (pintype "passive"))
      (node (ref "P19") (pin "4") (pinfunction "4_4") (pintype "passive"))
      (node (ref "P2") (pin "1") (pinfunction "1_1") (pintype "passive"))
      (node (ref "P2") (pin "20") (pinfunction "20_20") (pintype "passive"))
      (node (ref "P20") (pin "4") (pinfunction "4_4") (pintype "passive"))
      (node (ref "P3") (pin "2") (pinfunction "2_2") (pintype "passive"))
      (node (ref "P4") (pin "2") (pinfunction "2_2") (pintype "passive"))
      (node (ref "P5") (pin "1") (pinfunction "1_1") (pintype "passive"))
      (node (ref "P5") (pin "5") (pinfunction "5_5") (pintype "passive"))
      (node (ref "P6") (pin "1") (pinfunction "1_1") (pintype "passive"))
      (node (ref "P7") (pin "2") (pinfunction "2_2") (pintype "passive"))
      (node (ref "P8") (pin "2") (pinfunction "2_2") (pintype "passive"))
      (node (ref "Q1") (pin "2") (pinfunction "E_2") (pintype "passive"))
      (node (ref "Q2") (pin "2") (pinfunction "E_2") (pintype "passive"))
      (node (ref "Q3") (pin "1") (pinfunction "C_1") (pintype "passive"))
      (node (ref "Q4") (pin "1") (pinfunction "C_1") (pintype "passive"))
      (node (ref "Q5") (pin "2") (pinfunction "E_2") (pintype "passive"))
      (node (ref "Q6") (pin "2") (pinfunction "E_2") (pintype "passive"))
      (node (ref "Q7") (pin "2") (pinfunction "E_2") (pintype "passive"))
      (node (ref "R10") (pin "1") (pinfunction "1_1") (pintype "passive"))
      (node (ref "R15") (pin "1") (pinfunction "1_1") (pintype "passive"))
      (node (ref "R2") (pin "1") (pinfunction "1_1") (pintype "passive"))
      (node (ref "R29") (pin "2") (pinfunction "2_2") (pintype "passive"))
      (node (ref "R31") (pin "1") (pinfunction "1_1") (pintype "passive"))
      (node (ref "R37") (pin "1") (pinfunction "1_1") (pintype "passive"))
      (node (ref "U1") (pin "4") (pinfunction "GND_4") (pintype "passive"))
      (node (ref "U10") (pin "2") (pintype "passive"))
      (node (ref "U11") (pin "4") (pinfunction "V-_4") (pintype "power_in"))
      (node (ref "U2") (pin "21") (pinfunction "VSS_21") (pintype "passive"))
      (node (ref "U2") (pin "45") (pinfunction "VSSAD_45") (pintype "passive"))
      (node (ref "U2") (pin "55") (pinfunction "VRFL_55") (pintype "passive"))
      (node (ref "U2") (pin "59") (pinfunction "VSS_59") (pintype "passive"))
      (node (ref "U3") (pin "3") (pinfunction "GND_3") (pintype "power_in"))
      (node (ref "U3") (pin "6") (pinfunction "TAB_6") (pintype "power_in"))
      (node (ref "U4") (pin "1") (pinfunction "A0_1") (pintype "input"))
      (node (ref "U4") (pin "2") (pinfunction "A1_2") (pintype "input"))
      (node (ref "U4") (pin "3") (pinfunction "A2_3") (pintype "input"))
      (node (ref "U4") (pin "4") (pinfunction "VSS_4") (pintype "power_in"))
      (node (ref "U4") (pin "7") (pinfunction "WP_7") (pintype "input"))
      (node (ref "U5") (pin "5") (pinfunction "GND_5") (pintype "power_in"))
      (node (ref "U6") (pin "2") (pinfunction "GND_2") (pintype "passive"))
      (node (ref "U6") (pin "4") (pinfunction "GND_4") (pintype "passive"))
      (node (ref "U7") (pin "15") (pinfunction "GND_15") (pintype "power_in"))
      (node (ref "U8") (pin "6") (pinfunction "~{EN}_6") (pintype "input"))
      (node (ref "U8") (pin "7") (pinfunction "VEE_7") (pintype "power_in"))
      (node (ref "U8") (pin "8") (pinfunction "GND_8") (pintype "power_in"))
      (node (ref "U9") (pin "5") (pinfunction "GND_5") (pintype "power_in"))
    )
    (net (code "79") (name "Net-(BT1-+)") (class "Default")
      (node (ref "BT1") (pin "1") (pinfunction "+_1") (pintype "passive"))
      (node (ref "C4") (pin "2") (pinfunction "2_2") (pintype "passive"))
      (node (ref "U1") (pin "3") (pinfunction "VABT_3") (pintype "passive"))
    )
    (net (code "80") (name "Net-(D1-K)") (class "Default")
      (node (ref "D1") (pin "2") (pinfunction "K_2") (pintype "passive"))
      (node (ref "F1") (pin "1") (pinfunction "1_1") (pintype "passive"))
    )
    (net (code "81") (name "Net-(D3-K)") (class "Default")
      (node (ref "D3") (pin "2") (pinfunction "K_2") (pintype "passive"))
      (node (ref "L1") (pin "1") (pinfunction "1_1") (pintype "passive"))
      (node (ref "U3") (pin "2") (pinfunction "OUT_2") (pintype "power_in"))
    )
    (net (code "82") (name "Net-(D6-A)") (class "Default")
      (node (ref "D6") (pin "1") (pinfunction "A_1") (pintype "passive"))
      (node (ref "R4") (pin "1") (pinfunction "1_1") (pintype "passive"))
    )
    (net (code "83") (name "Net-(D7-A)") (class "Default")
      (node (ref "D7") (pin "1") (pinfunction "A_1") (pintype "passive"))
      (node (ref "R9") (pin "1") (pinfunction "1_1") (pintype "passive"))
    )
    (net (code "84") (name "Net-(D8-K)") (class "Default")
      (node (ref "C20") (pin "1") (pinfunction "1_1") (pintype "passive"))
      (node (ref "C22") (pin "2") (pinfunction "2_2") (pintype "passive"))
      (node (ref "D8") (pin "2") (pinfunction "K_2") (pintype "passive"))
      (node (ref "F2") (pin "2") (pinfunction "2_2") (pintype "passive"))
      (node (ref "U6") (pin "1") (pinfunction "IN_1") (pintype "passive"))
    )
    (net (code "85") (name "Net-(D10-K)") (class "Default")
      (node (ref "D10") (pin "2") (pinfunction "K_2") (pintype "passive"))
      (node (ref "D11") (pin "1") (pinfunction "A_1") (pintype "passive"))
      (node (ref "P7") (pin "3") (pinfunction "3_3") (pintype "passive"))
      (node (ref "P8") (pin "3") (pinfunction "3_3") (pintype "passive"))
      (node (ref "PTC1") (pin "2") (pinfunction "2_2") (pintype "passive"))
    )
    (net (code "86") (name "Net-(D11-K)") (class "Default")
      (node (ref "D11") (pin "2") (pinfunction "K_2") (pintype "passive"))
      (node (ref "D12") (pin "2") (pinfunction "K_2") (pintype "passive"))
      (node (ref "P7") (pin "4") (pinfunction "4_4") (pintype "passive"))
      (node (ref "P8") (pin "4") (pinfunction "4_4") (pintype "passive"))
      (node (ref "PTC2") (pin "2") (pinfunction "2_2") (pintype "passive"))
    )
    (net (code "87") (name "Net-(D14-K)") (class "Default")
      (node (ref "D14") (pin "2") (pinfunction "K_2") (pintype "passive"))
      (node (ref "RP2") (pin "7") (pinfunction "7_7") (pintype "passive"))
    )
    (net (code "88") (name "Net-(D15-K)") (class "Default")
      (node (ref "D15") (pin "2") (pinfunction "K_2") (pintype "passive"))
      (node (ref "RP2") (pin "5") (pinfunction "5_5") (pintype "passive"))
    )
    (net (code "89") (name "Net-(D16-K)") (class "Default")
      (node (ref "D16") (pin "2") (pinfunction "K_2") (pintype "passive"))
      (node (ref "RP2") (pin "8") (pinfunction "8_8") (pintype "passive"))
    )
    (net (code "90") (name "Net-(D17-K)") (class "Default")
      (node (ref "D17") (pin "2") (pinfunction "K_2") (pintype "passive"))
      (node (ref "RP2") (pin "6") (pinfunction "6_6") (pintype "passive"))
    )
    (net (code "91") (name "Net-(J1-Pad9)") (class "Default")
      (node (ref "J1") (pin "9") (pinfunction "9_9") (pintype "passive"))
      (node (ref "R20") (pin "1") (pinfunction "1_1") (pintype "passive"))
    )
    (net (code "92") (name "Net-(P10-Pad1)") (class "Default")
      (node (ref "P10") (pin "1") (pinfunction "1_1") (pintype "passive"))
      (node (ref "RP1") (pin "1") (pinfunction "1_1") (pintype "passive"))
    )
    (net (code "93") (name "Net-(P10-Pad2)") (class "Default")
      (node (ref "P10") (pin "2") (pinfunction "2_2") (pintype "passive"))
      (node (ref "RP1") (pin "2") (pinfunction "2_2") (pintype "passive"))
    )
    (net (code "94") (name "Net-(P10-Pad3)") (class "Default")
      (node (ref "P10") (pin "3") (pinfunction "3_3") (pintype "passive"))
      (node (ref "RP1") (pin "3") (pinfunction "3_3") (pintype "passive"))
    )
    (net (code "95") (name "Net-(P10-Pad4)") (class "Default")
      (node (ref "P10") (pin "4") (pinfunction "4_4") (pintype "passive"))
      (node (ref "RP1") (pin "4") (pinfunction "4_4") (pintype "passive"))
    )
    (net (code "96") (name "Net-(P10-Pad5)") (class "Default")
      (node (ref "P10") (pin "5") (pinfunction "5_5") (pintype "passive"))
      (node (ref "RP2") (pin "1") (pinfunction "1_1") (pintype "passive"))
      (node (ref "RP3") (pin "1") (pinfunction "1_1") (pintype "passive"))
      (node (ref "U10") (pin "4") (pintype "passive"))
    )
    (net (code "97") (name "Net-(P10-Pad6)") (class "Default")
      (node (ref "P10") (pin "6") (pinfunction "6_6") (pintype "passive"))
      (node (ref "RP2") (pin "2") (pinfunction "2_2") (pintype "passive"))
      (node (ref "RP3") (pin "2") (pinfunction "2_2") (pintype "passive"))
      (node (ref "U10") (pin "6") (pintype "passive"))
    )
    (net (code "98") (name "Net-(P10-Pad7)") (class "Default")
      (node (ref "P10") (pin "7") (pinfunction "7_7") (pintype "passive"))
      (node (ref "RP2") (pin "3") (pinfunction "3_3") (pintype "passive"))
      (node (ref "RP3") (pin "3") (pinfunction "3_3") (pintype "passive"))
      (node (ref "U10") (pin "1") (pintype "passive"))
    )
    (net (code "99") (name "Net-(P10-Pad8)") (class "Default")
      (node (ref "P10") (pin "8") (pinfunction "8_8") (pintype "passive"))
      (node (ref "RP2") (pin "4") (pinfunction "4_4") (pintype "passive"))
      (node (ref "RP3") (pin "4") (pinfunction "4_4") (pintype "passive"))
      (node (ref "U10") (pin "3") (pintype "passive"))
    )
    (net (code "100") (name "Net-(Q1-B)") (class "Default")
      (node (ref "Q1") (pin "1") (pinfunction "B_1") (pintype "passive"))
      (node (ref "R10") (pin "2") (pinfunction "2_2") (pintype "passive"))
      (node (ref "R7") (pin "2") (pinfunction "2_2") (pintype "passive"))
    )
    (net (code "101") (name "Net-(Q1-C)") (class "Default")
      (node (ref "Q1") (pin "3") (pinfunction "C_3") (pintype "passive"))
      (node (ref "R38") (pin "1") (pinfunction "1_1") (pintype "passive"))
    )
    (net (code "102") (name "Net-(Q2-C)") (class "Default")
      (node (ref "P5") (pin "3") (pinfunction "3_3") (pintype "passive"))
      (node (ref "Q2") (pin "3") (pinfunction "C_3") (pintype "passive"))
    )
    (net (code "103") (name "Net-(Q3-B)") (class "Default")
      (node (ref "PTC1") (pin "1") (pinfunction "1_1") (pintype "passive"))
      (node (ref "Q3") (pin "3") (pinfunction "B_3") (pintype "passive"))
      (node (ref "R13") (pin "1") (pinfunction "1_1") (pintype "passive"))
      (node (ref "R14") (pin "2") (pinfunction "2_2") (pintype "passive"))
      (node (ref "U5") (pin "6") (pinfunction "A_6") (pintype "bidirectional"))
    )
    (net (code "104") (name "Net-(Q4-B)") (class "Default")
      (node (ref "PTC2") (pin "1") (pinfunction "1_1") (pintype "passive"))
      (node (ref "Q4") (pin "3") (pinfunction "B_3") (pintype "passive"))
      (node (ref "R14") (pin "1") (pinfunction "1_1") (pintype "passive"))
      (node (ref "R15") (pin "2") (pinfunction "2_2") (pintype "passive"))
      (node (ref "U5") (pin "7") (pinfunction "B_7") (pintype "bidirectional"))
    )
    (net (code "105") (name "Net-(Q5-B)") (class "Default")
      (node (ref "Q5") (pin "1") (pinfunction "B_1") (pintype "passive"))
      (node (ref "R21") (pin "2") (pinfunction "2_2") (pintype "passive"))
    )
    (net (code "106") (name "Net-(Q6-B)") (class "Default")
      (node (ref "Q6") (pin "1") (pinfunction "B_1") (pintype "passive"))
      (node (ref "R24") (pin "2") (pinfunction "2_2") (pintype "passive"))
    )
    (net (code "107") (name "Net-(Q7-B)") (class "Default")
      (node (ref "Q7") (pin "1") (pinfunction "B_1") (pintype "passive"))
      (node (ref "R35") (pin "2") (pinfunction "2_2") (pintype "passive"))
    )
    (net (code "108") (name "Net-(Q7-C)") (class "Default")
      (node (ref "LS1") (pin "2") (pinfunction "2_2") (pintype "passive"))
      (node (ref "Q7") (pin "3") (pinfunction "C_3") (pintype "passive"))
    )
    (net (code "109") (name "Net-(Q8-D)") (class "Default")
      (node (ref "P6") (pin "3") (pinfunction "3_3") (pintype "passive"))
      (node (ref "Q8") (pin "3") (pinfunction "D_3") (pintype "passive"))
    )
    (net (code "110") (name "Net-(Q8-G)") (class "Default")
      (node (ref "Q8") (pin "1") (pinfunction "G_1") (pintype "passive"))
      (node (ref "R12") (pin "1") (pinfunction "1_1") (pintype "passive"))
      (node (ref "R38") (pin "2") (pinfunction "2_2") (pintype "passive"))
    )
    (net (code "111") (name "Net-(U1-OSCIN)") (class "Default")
      (node (ref "C5") (pin "1") (pinfunction "1_1") (pintype "passive"))
      (node (ref "U1") (pin "1") (pinfunction "OSCIN_1") (pintype "passive"))
      (node (ref "Y1") (pin "2") (pinfunction "OSC2_2") (pintype "passive"))
    )
    (net (code "112") (name "Net-(U1-OSCOUT)") (class "Default")
      (node (ref "C3") (pin "1") (pinfunction "1_1") (pintype "passive"))
      (node (ref "U1") (pin "2") (pinfunction "OSCOUT_2") (pintype "passive"))
      (node (ref "Y1") (pin "1") (pinfunction "OSC1_1") (pintype "passive"))
    )
    (net (code "113") (name "Net-(U2-EXTAL{slash}PTG6)") (class "Default")
      (node (ref "C16") (pin "2") (pinfunction "2_2") (pintype "passive"))
      (node (ref "R3") (pin "2") (pinfunction "2_2") (pintype "passive"))
      (node (ref "U2") (pin "58") (pinfunction "EXTAL/PTG6_58") (pintype "bidirectional"))
      (node (ref "Y2") (pin "2") (pinfunction "OSC2_2") (pintype "passive"))
    )
    (net (code "114") (name "Net-(U2-XTAL{slash}PTG5)") (class "Default")
      (node (ref "C13") (pin "2") (pinfunction "2_2") (pintype "passive"))
      (node (ref "R3") (pin "1") (pinfunction "1_1") (pintype "passive"))
      (node (ref "U2") (pin "57") (pinfunction "XTAL/PTG5_57") (pintype "bidirectional"))
      (node (ref "Y2") (pin "1") (pinfunction "OSC1_1") (pintype "passive"))
    )
    (net (code "115") (name "Net-(U3-~{ON}{slash}OFF)") (class "Default")
      (node (ref "R2") (pin "2") (pinfunction "2_2") (pintype "passive"))
      (node (ref "U3") (pin "5") (pinfunction "~{ON}/OFF_5") (pintype "input"))
    )
    (net (code "116") (name "Net-(U7-C1+)") (class "Default")
      (node (ref "C21") (pin "2") (pinfunction "2_2") (pintype "passive"))
      (node (ref "U7") (pin "1") (pinfunction "C1+_1") (pintype "passive"))
    )
    (net (code "117") (name "Net-(U7-C1-)") (class "Default")
      (node (ref "C21") (pin "1") (pinfunction "1_1") (pintype "passive"))
      (node (ref "U7") (pin "3") (pinfunction "C1-_3") (pintype "passive"))
    )
    (net (code "118") (name "Net-(U7-C2+)") (class "Default")
      (node (ref "C19") (pin "2") (pinfunction "2_2") (pintype "passive"))
      (node (ref "U7") (pin "4") (pinfunction "C2+_4") (pintype "passive"))
    )
    (net (code "119") (name "Net-(U7-C2-)") (class "Default")
      (node (ref "C19") (pin "1") (pinfunction "1_1") (pintype "passive"))
      (node (ref "U7") (pin "5") (pinfunction "C2-_5") (pintype "passive"))
    )
    (net (code "120") (name "Net-(U7-V+)") (class "Default")
      (node (ref "C26") (pin "1") (pinfunction "1_1") (pintype "passive"))
      (node (ref "U7") (pin "2") (pinfunction "V+_2") (pintype "power_in"))
    )
    (net (code "121") (name "Net-(U7-V-)") (class "Default")
      (node (ref "C23") (pin "2") (pinfunction "2_2") (pintype "passive"))
      (node (ref "U7") (pin "6") (pinfunction "V-_6") (pintype "power_in"))
    )
    (net (code "122") (name "Net-(U9-PWM1)") (class "Default")
      (node (ref "P9") (pin "1") (pinfunction "1_1") (pintype "passive"))
      (node (ref "U9") (pin "3") (pinfunction "PWM1_3") (pintype "output"))
    )
    (net (code "123") (name "Net-(U9-PWM2)") (class "Default")
      (node (ref "P9") (pin "2") (pinfunction "2_2") (pintype "passive"))
      (node (ref "U9") (pin "2") (pinfunction "PWM2_2") (pintype "output"))
    )
    (net (code "124") (name "Net-(U9-VREG)") (class "Default")
      (node (ref "C34") (pin "1") (pinfunction "1_1") (pintype "passive"))
      (node (ref "U9") (pin "1") (pinfunction "VREG_1") (pintype "power_in"))
    )
    (net (code "125") (name "Net-(U11A-IN+)") (class "Default")
      (node (ref "C38") (pin "2") (pinfunction "2_2") (pintype "passive"))
      (node (ref "R28") (pin "2") (pinfunction "2_2") (pintype "passive"))
      (node (ref "U11") (pin "3") (pinfunction "IN+_3") (pintype "input"))
    )
    (net (code "126") (name "Net-(U11A-IN-)") (class "Default")
      (node (ref "R30") (pin "1") (pinfunction "1_1") (pintype "passive"))
      (node (ref "R31") (pin "2") (pinfunction "2_2") (pintype "passive"))
      (node (ref "U11") (pin "2") (pinfunction "IN-_2") (pintype "input"))
    )
    (net (code "127") (name "VCC") (class "Default")
      (node (ref "C10") (pin "1") (pinfunction "1_1") (pintype "passive"))
      (node (ref "C14") (pin "2") (pinfunction "2_2") (pintype "passive"))
      (node (ref "C15") (pin "2") (pinfunction "2_2") (pintype "passive"))
      (node (ref "C17") (pin "2") (pinfunction "2_2") (pintype "passive"))
      (node (ref "C18") (pin "2") (pinfunction "2_2") (pintype "passive"))
      (node (ref "C24") (pin "1") (pinfunction "1_1") (pintype "passive"))
      (node (ref "C26") (pin "2") (pinfunction "2_2") (pintype "passive"))
      (node (ref "C30") (pin "2") (pinfunction "2_2") (pintype "passive"))
      (node (ref "C33") (pin "2") (pinfunction "2_2") (pintype "passive"))
      (node (ref "C35") (pin "1") (pinfunction "1_1") (pintype "passive"))
      (node (ref "C36") (pin "2") (pinfunction "2_2") (pintype "passive"))
      (node (ref "C42") (pin "1") (pinfunction "1_1") (pintype "passive"))
      (node (ref "C9") (pin "1") (pinfunction "1_1") (pintype "passive"))
      (node (ref "L2") (pin "2") (pinfunction "2_2") (pintype "passive"))
      (node (ref "P4") (pin "6") (pinfunction "6_6") (pintype "passive"))
      (node (ref "Q3") (pin "2") (pinfunction "E_2") (pintype "passive"))
      (node (ref "Q4") (pin "2") (pinfunction "E_2") (pintype "passive"))
      (node (ref "R1") (pin "2") (pinfunction "2_2") (pintype "passive"))
      (node (ref "R13") (pin "2") (pinfunction "2_2") (pintype "passive"))
      (node (ref "R16") (pin "2") (pinfunction "2_2") (pintype "passive"))
      (node (ref "R17") (pin "2") (pinfunction "2_2") (pintype "passive"))
      (node (ref "R18") (pin "2") (pinfunction "2_2") (pintype "passive"))
      (node (ref "R19") (pin "2") (pinfunction "2_2") (pintype "passive"))
      (node (ref "R22") (pin "2") (pinfunction "2_2") (pintype "passive"))
      (node (ref "R23") (pin "2") (pinfunction "2_2") (pintype "passive"))
      (node (ref "R26") (pin "2") (pinfunction "2_2") (pintype "passive"))
      (node (ref "R27") (pin "2") (pinfunction "2_2") (pintype "passive"))
      (node (ref "R30") (pin "2") (pinfunction "2_2") (pintype "passive"))
      (node (ref "R32") (pin "2") (pinfunction "2_2") (pintype "passive"))
      (node (ref "R33") (pin "2") (pinfunction "2_2") (pintype "passive"))
      (node (ref "R34") (pin "2") (pinfunction "2_2") (pintype "passive"))
      (node (ref "R36") (pin "2") (pinfunction "2_2") (pintype "passive"))
      (node (ref "R5") (pin "2") (pinfunction "2_2") (pintype "passive"))
      (node (ref "R6") (pin "2") (pinfunction "2_2") (pintype "passive"))
      (node (ref "R9") (pin "2") (pinfunction "2_2") (pintype "passive"))
      (node (ref "RP3") (pin "5") (pinfunction "5_5") (pintype "passive"))
      (node (ref "RP3") (pin "6") (pinfunction "6_6") (pintype "passive"))
      (node (ref "RP3") (pin "7") (pinfunction "7_7") (pintype "passive"))
      (node (ref "RP3") (pin "8") (pinfunction "8_8") (pintype "passive"))
      (node (ref "U1") (pin "8") (pinfunction "VDD_8") (pintype "passive"))
      (node (ref "U10") (pin "5") (pintype "passive"))
      (node (ref "U11") (pin "8") (pinfunction "V+_8") (pintype "power_in"))
      (node (ref "U2") (pin "22") (pinfunction "VDD_22") (pintype "passive"))
      (node (ref "U2") (pin "44") (pinfunction "VDDAD_44") (pintype "passive"))
      (node (ref "U2") (pin "54") (pinfunction "VRFH_54") (pintype "passive"))
      (node (ref "U4") (pin "8") (pinfunction "VCC_8") (pintype "power_in"))
      (node (ref "U5") (pin "8") (pinfunction "VCC_8") (pintype "power_in"))
      (node (ref "U7") (pin "16") (pinfunction "VCC_16") (pintype "power_in"))
      (node (ref "U8") (pin "16") (pinfunction "VCC_16") (pintype "power_in"))
      (node (ref "U9") (pin "4") (pinfunction "VDD_4") (pintype "power_in"))
    )
    (net (code "128") (name "unconnected-(J1-MH1-Pad10)") (class "Default")
      (node (ref "J1") (pin "10") (pinfunction "MH1_10") (pintype "passive+no_connect"))
    )
    (net (code "129") (name "unconnected-(J1-MH2-Pad11)") (class "Default")
      (node (ref "J1") (pin "11") (pinfunction "MH2_11") (pintype "passive+no_connect"))
    )
    (net (code "130") (name "unconnected-(J1-Pad1)") (class "Default")
      (node (ref "J1") (pin "1") (pinfunction "1_1") (pintype "passive+no_connect"))
    )
    (net (code "131") (name "unconnected-(J1-Pad4)") (class "Default")
      (node (ref "J1") (pin "4") (pinfunction "4_4") (pintype "passive+no_connect"))
    )
    (net (code "132") (name "unconnected-(J1-Pad6)") (class "Default")
      (node (ref "J1") (pin "6") (pinfunction "6_6") (pintype "passive+no_connect"))
    )
    (net (code "133") (name "unconnected-(J1-Pad7)") (class "Default")
      (node (ref "J1") (pin "7") (pinfunction "7_7") (pintype "passive+no_connect"))
    )
    (net (code "134") (name "unconnected-(J1-Pad8)") (class "Default")
      (node (ref "J1") (pin "8") (pinfunction "8_8") (pintype "passive+no_connect"))
    )
    (net (code "135") (name "unconnected-(P2-Pad3)") (class "Default")
      (node (ref "P2") (pin "3") (pinfunction "3_3") (pintype "passive+no_connect"))
    )
    (net (code "136") (name "unconnected-(P2-Pad16)") (class "Default")
      (node (ref "P2") (pin "16") (pinfunction "16_16") (pintype "passive+no_connect"))
    )
    (net (code "137") (name "unconnected-(P2-Pad18)") (class "Default")
      (node (ref "P2") (pin "18") (pinfunction "18_18") (pintype "passive+no_connect"))
    )
    (net (code "138") (name "unconnected-(P4-Pad3)") (class "Default")
      (node (ref "P4") (pin "3") (pinfunction "3_3") (pintype "passive+no_connect"))
    )
    (net (code "139") (name "unconnected-(P4-Pad5)") (class "Default")
      (node (ref "P4") (pin "5") (pinfunction "5_5") (pintype "passive+no_connect"))
    )
    (net (code "140") (name "unconnected-(U1-INT-Pad7)") (class "Default")
      (node (ref "U1") (pin "7") (pinfunction "INT_7") (pintype "passive+no_connect"))
    )
  )
)
